# TesterMotorFaulhaber.net
KiCad netlist of a schematic drawn in EAGLE
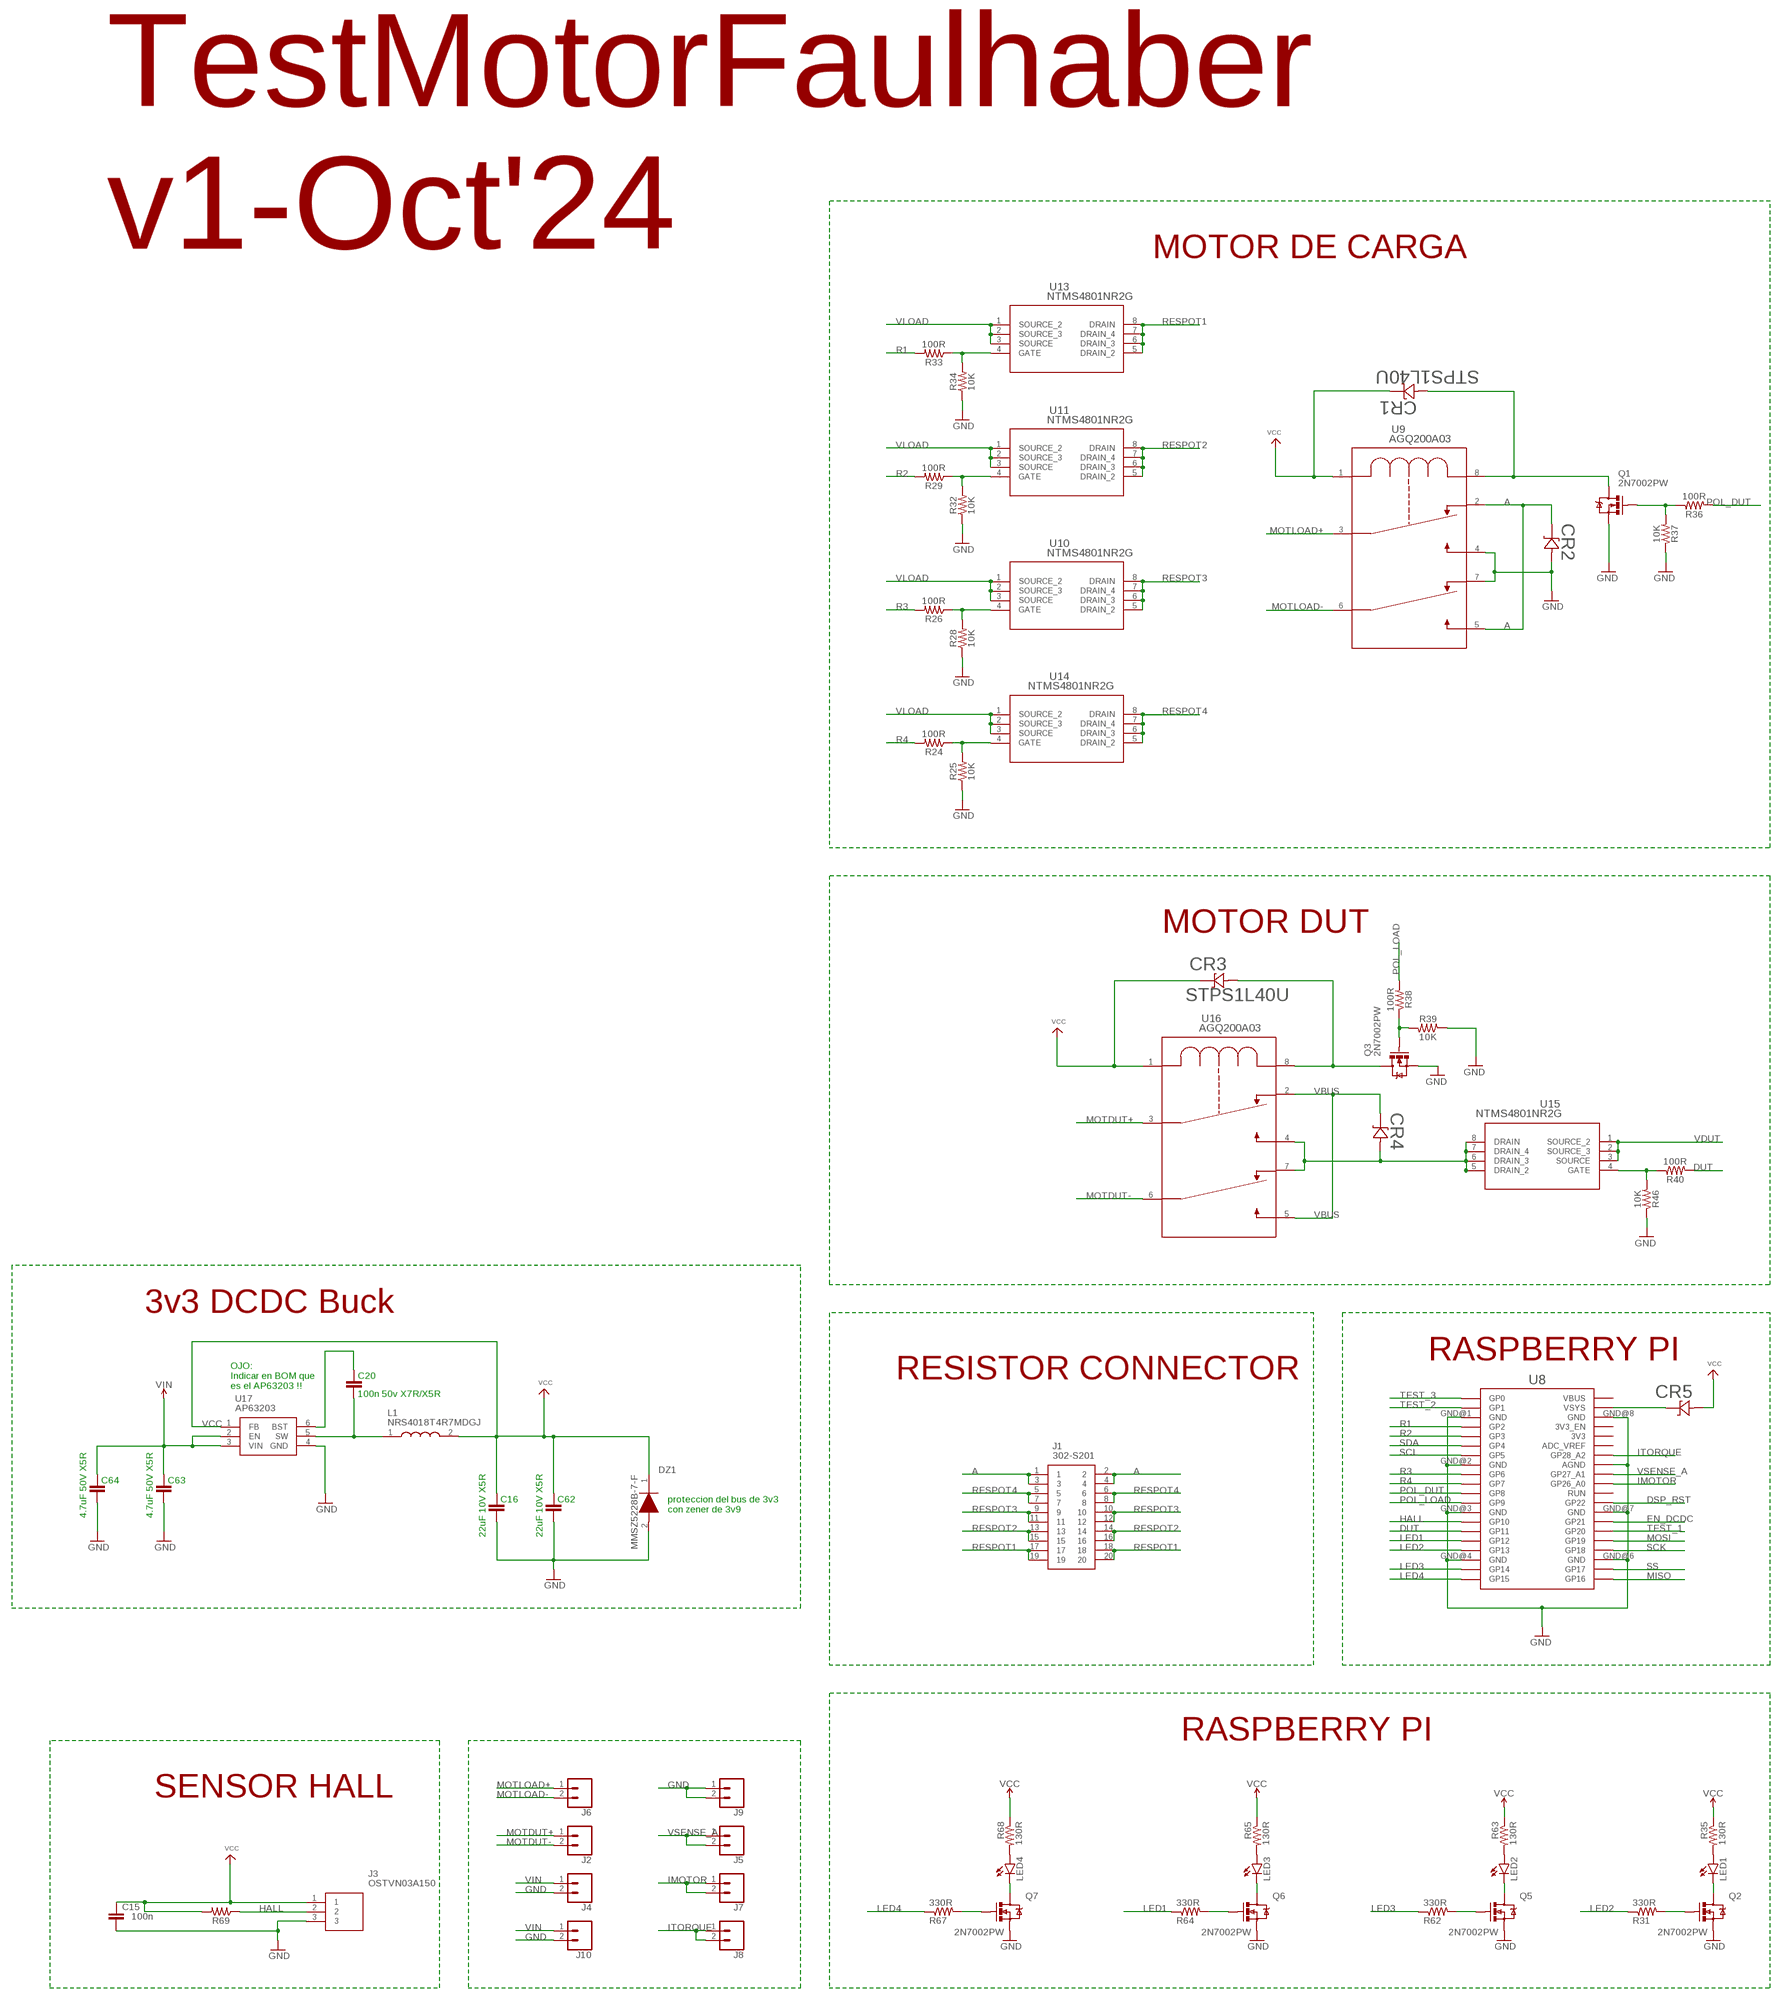
[diagram p0: schematic, sheet 1, part 1 of 2]
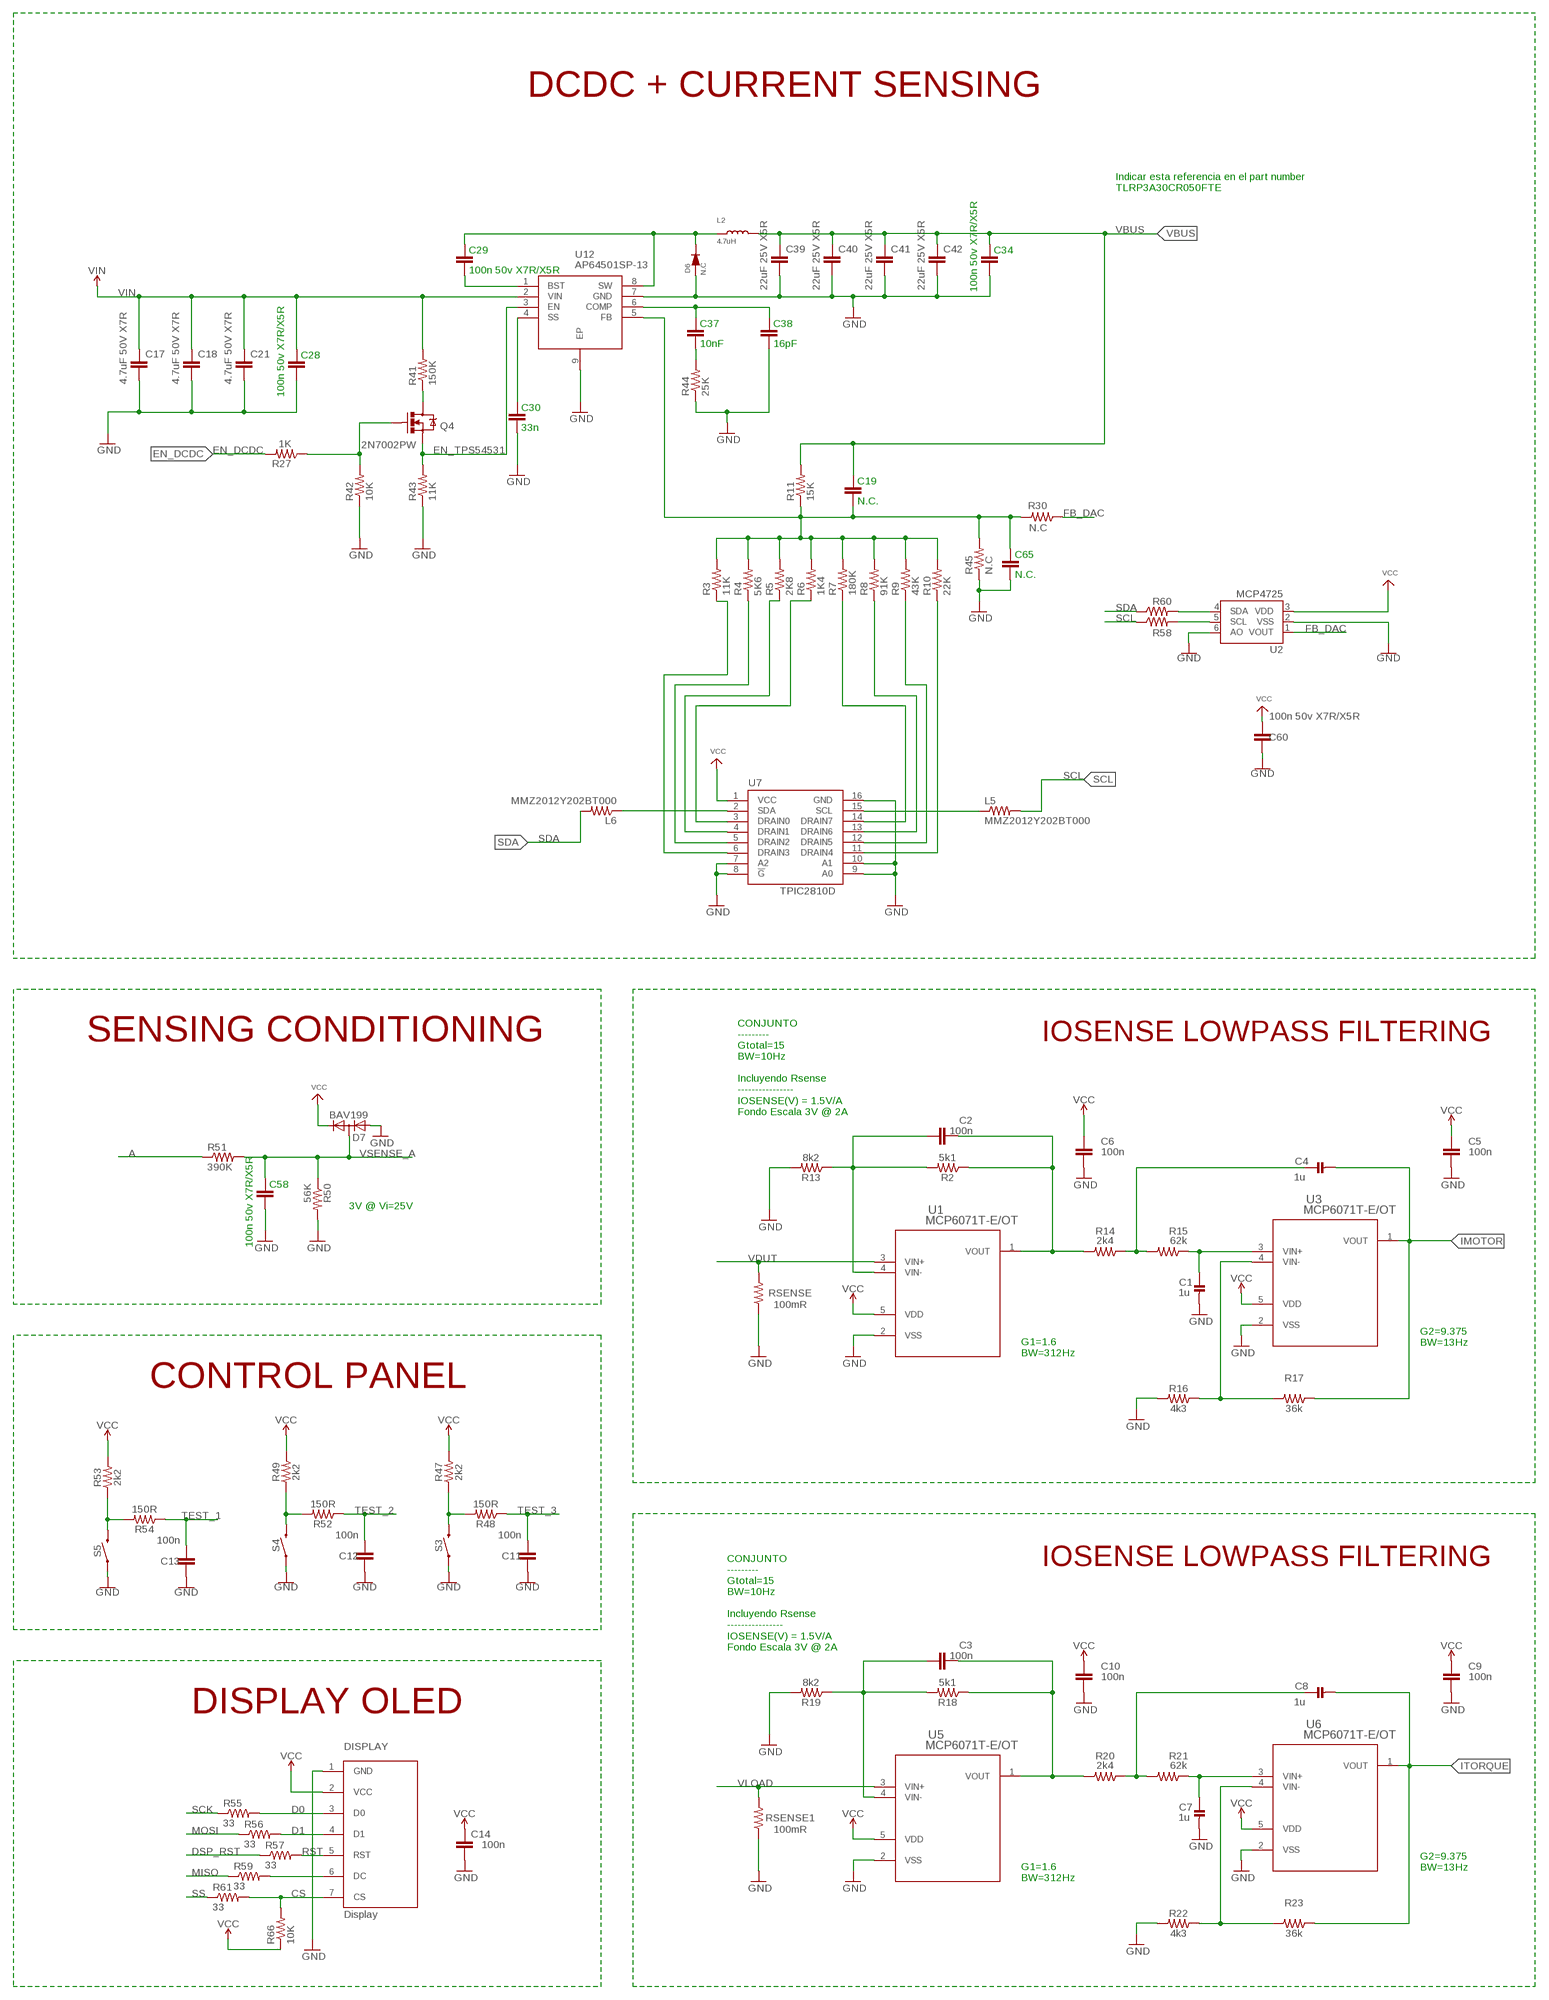
[diagram p1: schematic, sheet 1, part 2 of 2]

(export (version "E")
  (design (tool "Eeschema 10.0.6"))
  (components
    (comp (ref "C1")
      (value "1u")
      (footprint "eagle-import:0603-NO")
      (libsource (lib "eagle-import") (part "CAP_CERAMIC0603_NO"))
    )
    (comp (ref "C2")
      (value "100n")
      (footprint "eagle-import:0603")
      (libsource (lib "eagle-import") (part "0.1UF-0603-25V-(+80/-20%)"))
    )
    (comp (ref "C3")
      (value "100n")
      (footprint "eagle-import:0603")
      (libsource (lib "eagle-import") (part "0.1UF-0603-25V-(+80/-20%)"))
    )
    (comp (ref "C4")
      (value "1u")
      (footprint "eagle-import:0603-NO")
      (libsource (lib "eagle-import") (part "CAP_CERAMIC0603_NO"))
    )
    (comp (ref "C5")
      (value "100n")
      (footprint "eagle-import:0603")
      (libsource (lib "eagle-import") (part "0.1UF-0603-25V-(+80/-20%)"))
    )
    (comp (ref "C6")
      (value "100n")
      (footprint "eagle-import:0603")
      (libsource (lib "eagle-import") (part "0.1UF-0603-25V-(+80/-20%)"))
    )
    (comp (ref "C7")
      (value "1u")
      (footprint "eagle-import:0603-NO")
      (libsource (lib "eagle-import") (part "CAP_CERAMIC0603_NO"))
    )
    (comp (ref "C8")
      (value "1u")
      (footprint "eagle-import:0603-NO")
      (libsource (lib "eagle-import") (part "CAP_CERAMIC0603_NO"))
    )
    (comp (ref "C9")
      (value "100n")
      (footprint "eagle-import:0603")
      (libsource (lib "eagle-import") (part "0.1UF-0603-25V-(+80/-20%)"))
    )
    (comp (ref "C10")
      (value "100n")
      (footprint "eagle-import:0603")
      (libsource (lib "eagle-import") (part "0.1UF-0603-25V-(+80/-20%)"))
    )
    (comp (ref "C11")
      (value "100n")
      (footprint "eagle-import:0805")
      (libsource (lib "eagle-import") (part "1.0UF-0805-25V-(+80/-20%)"))
    )
    (comp (ref "C12")
      (value "100n")
      (footprint "eagle-import:0805")
      (libsource (lib "eagle-import") (part "1.0UF-0805-25V-(+80/-20%)"))
    )
    (comp (ref "C13")
      (value "100n")
      (footprint "eagle-import:0805")
      (libsource (lib "eagle-import") (part "1.0UF-0805-25V-(+80/-20%)"))
    )
    (comp (ref "C14")
      (value "100n")
      (footprint "eagle-import:0805")
      (libsource (lib "eagle-import") (part "1.0UF-0805-25V-(+80/-20%)"))
    )
    (comp (ref "C15")
      (value "100n")
      (footprint "eagle-import:0805")
      (libsource (lib "eagle-import") (part "1.0UF-0805-25V-(+80/-20%)"))
    )
    (comp (ref "C16")
      (value "22uF 10V X5R")
      (footprint "eagle-import:0805")
      (libsource (lib "eagle-import") (part "CAP0805"))
    )
    (comp (ref "C17")
      (value "4.7uF 50V X7R")
      (footprint "eagle-import:1210")
      (libsource (lib "eagle-import") (part "CAP1210"))
    )
    (comp (ref "C18")
      (value "4.7uF 50V X7R")
      (footprint "eagle-import:1210")
      (libsource (lib "eagle-import") (part "CAP1210"))
    )
    (comp (ref "C19")
      (value "N.C.")
      (footprint "eagle-import:0805")
      (libsource (lib "eagle-import") (part "CAP0805"))
    )
    (comp (ref "C20")
      (value "100n 50v X7R/X5R")
      (footprint "eagle-import:0805")
      (libsource (lib "eagle-import") (part "CAP0805"))
    )
    (comp (ref "C21")
      (value "4.7uF 50V X7R")
      (footprint "eagle-import:1210")
      (libsource (lib "eagle-import") (part "CAP1210"))
    )
    (comp (ref "C28")
      (value "100n 50v X7R/X5R")
      (footprint "eagle-import:0805")
      (libsource (lib "eagle-import") (part "CAP0805"))
    )
    (comp (ref "C29")
      (value "100n 50v X7R/X5R")
      (footprint "eagle-import:0805")
      (libsource (lib "eagle-import") (part "CAP0805"))
    )
    (comp (ref "C30")
      (value "33n")
      (footprint "eagle-import:0805")
      (libsource (lib "eagle-import") (part "CAP0805"))
    )
    (comp (ref "C34")
      (value "100n 50v X7R/X5R")
      (footprint "eagle-import:0805")
      (libsource (lib "eagle-import") (part "CAP0805"))
    )
    (comp (ref "C37")
      (value "10nF")
      (footprint "eagle-import:0805")
      (libsource (lib "eagle-import") (part "CAP0805"))
    )
    (comp (ref "C38")
      (value "16pF")
      (footprint "eagle-import:0805")
      (libsource (lib "eagle-import") (part "CAP0805"))
    )
    (comp (ref "C39")
      (value "22uF 25V X5R")
      (footprint "eagle-import:1210")
      (libsource (lib "eagle-import") (part "CAP1210"))
    )
    (comp (ref "C40")
      (value "22uF 25V X5R")
      (footprint "eagle-import:1210")
      (libsource (lib "eagle-import") (part "CAP1210"))
    )
    (comp (ref "C41")
      (value "22uF 25V X5R")
      (footprint "eagle-import:1210")
      (libsource (lib "eagle-import") (part "CAP1210"))
    )
    (comp (ref "C42")
      (value "22uF 25V X5R")
      (footprint "eagle-import:1210")
      (libsource (lib "eagle-import") (part "CAP1210"))
    )
    (comp (ref "C58")
      (value "100n 50v X7R/X5R")
      (footprint "eagle-import:0805")
      (libsource (lib "eagle-import") (part "CAP0805"))
    )
    (comp (ref "C60")
      (value "100n 50v X7R/X5R")
      (footprint "eagle-import:0805")
      (libsource (lib "eagle-import") (part "CAP0805"))
    )
    (comp (ref "C62")
      (value "22uF 10V X5R")
      (footprint "eagle-import:0805")
      (libsource (lib "eagle-import") (part "CAP0805"))
    )
    (comp (ref "C63")
      (value "4.7uF 50V X5R")
      (footprint "eagle-import:0805")
      (libsource (lib "eagle-import") (part "CAP0805"))
    )
    (comp (ref "C64")
      (value "4.7uF 50V X5R")
      (footprint "eagle-import:0805")
      (libsource (lib "eagle-import") (part "CAP0805"))
    )
    (comp (ref "C65")
      (value "N.C.")
      (footprint "eagle-import:0805")
      (libsource (lib "eagle-import") (part "CAP0805"))
    )
    (comp (ref "CR1")
      (value "STPS1L40U")
      (footprint "eagle-import:SMB_STM")
      (fields (field (name "COPYRIGHT") "Copyright (C) 2024 Ultra Librarian. All rights reserved."))
      (libsource (lib "eagle-import") (part "STPS1L40U"))
    )
    (comp (ref "CR2")
      (value "STPS1L40U")
      (footprint "eagle-import:SMB_STM")
      (fields (field (name "COPYRIGHT") "Copyright (C) 2024 Ultra Librarian. All rights reserved."))
      (libsource (lib "eagle-import") (part "STPS1L40U"))
    )
    (comp (ref "CR3")
      (value "STPS1L40U")
      (footprint "eagle-import:SMB_STM")
      (fields (field (name "COPYRIGHT") "Copyright (C) 2024 Ultra Librarian. All rights reserved."))
      (libsource (lib "eagle-import") (part "STPS1L40U"))
    )
    (comp (ref "CR4")
      (value "STPS1L40U")
      (footprint "eagle-import:SMB_STM")
      (fields (field (name "COPYRIGHT") "Copyright (C) 2024 Ultra Librarian. All rights reserved."))
      (libsource (lib "eagle-import") (part "STPS1L40U"))
    )
    (comp (ref "CR5")
      (value "STPS1L40U")
      (footprint "eagle-import:SMB_STM")
      (fields (field (name "COPYRIGHT") "Copyright (C) 2024 Ultra Librarian. All rights reserved."))
      (libsource (lib "eagle-import") (part "STPS1L40U"))
    )
    (comp (ref "D6")
      (value "N.C")
      (footprint "eagle-import:DO-214AB")
      (libsource (lib "eagle-import") (part "DSMC"))
    )
    (comp (ref "D7")
      (value "BAV199")
      (footprint "eagle-import:SOT23")
      (libsource (lib "eagle-import") (part "BAV199"))
    )
    (comp (ref "DISPLAY")
      (value "Display")
      (footprint "eagle-import:OLED_LCD")
      (libsource (lib "eagle-import") (part "OLED_LCD"))
    )
    (comp (ref "DZ1")
      (value "MMSZ5228B-7-F")
      (footprint "eagle-import:SODFL3518X115N")
      (libsource (lib "eagle-import") (part "MMSZ5228B-7-F"))
    )
    (comp (ref "J1")
      (value "302-S201")
      (footprint "eagle-import:SHDR20W66P254_2X10_3300X905X90")
      (libsource (lib "eagle-import") (part "302-S201"))
    )
    (comp (ref "J2")
      (value "CONN_02")
      (footprint "eagle-import:1X02")
      (libsource (lib "eagle-import") (part "CONN_02"))
    )
    (comp (ref "J3")
      (value "OSTVN03A150")
      (footprint "eagle-import:OSTVN03A150")
      (libsource (lib "eagle-import") (part "OSTVN03A150"))
    )
    (comp (ref "J4")
      (value "CONN_02")
      (footprint "eagle-import:1X02")
      (libsource (lib "eagle-import") (part "CONN_02"))
    )
    (comp (ref "J5")
      (value "CONN_02")
      (footprint "eagle-import:1X02")
      (libsource (lib "eagle-import") (part "CONN_02"))
    )
    (comp (ref "J6")
      (value "CONN_02")
      (footprint "eagle-import:1X02")
      (libsource (lib "eagle-import") (part "CONN_02"))
    )
    (comp (ref "J7")
      (value "CONN_02")
      (footprint "eagle-import:1X02")
      (libsource (lib "eagle-import") (part "CONN_02"))
    )
    (comp (ref "J8")
      (value "CONN_02")
      (footprint "eagle-import:1X02")
      (libsource (lib "eagle-import") (part "CONN_02"))
    )
    (comp (ref "J9")
      (value "CONN_02")
      (footprint "eagle-import:1X02")
      (libsource (lib "eagle-import") (part "CONN_02"))
    )
    (comp (ref "J10")
      (value "CONN_02")
      (footprint "eagle-import:1X02")
      (libsource (lib "eagle-import") (part "CONN_02"))
    )
    (comp (ref "L1")
      (value "NRS4018T4R7MDGJ")
      (footprint "eagle-import:NRS4018T100MDGJ")
      (fields (field (name "MOUSER_PART_NUMBER") "963-NRS4018T4R7MDGJ"))
      (libsource (lib "eagle-import") (part "NRS4018T4R7MDGJ"))
    )
    (comp (ref "L2")
      (value "4.7uH")
      (footprint "eagle-import:WE-LHMI")
      (libsource (lib "eagle-import") (part "L74437368047"))
    )
    (comp (ref "L5")
      (value "MMZ2012Y202BT000")
      (footprint "eagle-import:0805")
      (libsource (lib "eagle-import") (part "RESISTOR0805-RES"))
    )
    (comp (ref "L6")
      (value "MMZ2012Y202BT000")
      (footprint "eagle-import:0805")
      (libsource (lib "eagle-import") (part "RESISTOR0805-RES"))
    )
    (comp (ref "LED1")
      (value "LED3MM")
      (footprint "eagle-import:LED3MM")
      (libsource (lib "eagle-import") (part "LED3MM"))
    )
    (comp (ref "LED2")
      (value "LED3MM")
      (footprint "eagle-import:LED3MM")
      (libsource (lib "eagle-import") (part "LED3MM"))
    )
    (comp (ref "LED3")
      (value "LED3MM")
      (footprint "eagle-import:LED3MM")
      (libsource (lib "eagle-import") (part "LED3MM"))
    )
    (comp (ref "LED4")
      (value "LED3MM")
      (footprint "eagle-import:LED3MM")
      (libsource (lib "eagle-import") (part "LED3MM"))
    )
    (comp (ref "Q1")
      (value "2N7002PW")
      (footprint "eagle-import:SOT323")
      (libsource (lib "eagle-import") (part "MOSFET-NCHANNEL2N7002PW"))
    )
    (comp (ref "Q2")
      (value "2N7002PW")
      (footprint "eagle-import:SOT323")
      (libsource (lib "eagle-import") (part "MOSFET-NCHANNEL2N7002PW"))
    )
    (comp (ref "Q3")
      (value "2N7002PW")
      (footprint "eagle-import:SOT323")
      (libsource (lib "eagle-import") (part "MOSFET-NCHANNEL2N7002PW"))
    )
    (comp (ref "Q4")
      (value "2N7002PW")
      (footprint "eagle-import:SOT323")
      (libsource (lib "eagle-import") (part "MOSFET-NCHANNEL2N7002PW"))
    )
    (comp (ref "Q5")
      (value "2N7002PW")
      (footprint "eagle-import:SOT323")
      (libsource (lib "eagle-import") (part "MOSFET-NCHANNEL2N7002PW"))
    )
    (comp (ref "Q6")
      (value "2N7002PW")
      (footprint "eagle-import:SOT323")
      (libsource (lib "eagle-import") (part "MOSFET-NCHANNEL2N7002PW"))
    )
    (comp (ref "Q7")
      (value "2N7002PW")
      (footprint "eagle-import:SOT323")
      (libsource (lib "eagle-import") (part "MOSFET-NCHANNEL2N7002PW"))
    )
    (comp (ref "R2")
      (value "5k1")
      (footprint "eagle-import:0805")
      (libsource (lib "eagle-import") (part "RESISTOR0805"))
    )
    (comp (ref "R3")
      (value "11K")
      (footprint "eagle-import:0805")
      (libsource (lib "eagle-import") (part "RESISTOR0805"))
    )
    (comp (ref "R4")
      (value "5K6")
      (footprint "eagle-import:0805")
      (libsource (lib "eagle-import") (part "RESISTOR0805"))
    )
    (comp (ref "R5")
      (value "2K8")
      (footprint "eagle-import:0805")
      (libsource (lib "eagle-import") (part "RESISTOR0805"))
    )
    (comp (ref "R6")
      (value "1K4")
      (footprint "eagle-import:0805")
      (libsource (lib "eagle-import") (part "RESISTOR0805"))
    )
    (comp (ref "R7")
      (value "180K")
      (footprint "eagle-import:0805")
      (libsource (lib "eagle-import") (part "RESISTOR0805"))
    )
    (comp (ref "R8")
      (value "91K")
      (footprint "eagle-import:0805")
      (libsource (lib "eagle-import") (part "RESISTOR0805"))
    )
    (comp (ref "R9")
      (value "43K")
      (footprint "eagle-import:0805")
      (libsource (lib "eagle-import") (part "RESISTOR0805"))
    )
    (comp (ref "R10")
      (value "22K")
      (footprint "eagle-import:0805")
      (libsource (lib "eagle-import") (part "RESISTOR0805"))
    )
    (comp (ref "R11")
      (value "15K")
      (footprint "eagle-import:0805")
      (libsource (lib "eagle-import") (part "RESISTOR0805"))
    )
    (comp (ref "R13")
      (value "8k2")
      (footprint "eagle-import:0805")
      (libsource (lib "eagle-import") (part "RESISTOR0805"))
    )
    (comp (ref "R14")
      (value "2k4")
      (footprint "eagle-import:0805")
      (libsource (lib "eagle-import") (part "RESISTOR0805"))
    )
    (comp (ref "R15")
      (value "62k")
      (footprint "eagle-import:0805")
      (libsource (lib "eagle-import") (part "RESISTOR0805"))
    )
    (comp (ref "R16")
      (value "4k3")
      (footprint "eagle-import:0805")
      (libsource (lib "eagle-import") (part "RESISTOR0805"))
    )
    (comp (ref "R17")
      (value "36k")
      (footprint "eagle-import:0805")
      (libsource (lib "eagle-import") (part "RESISTOR0805"))
    )
    (comp (ref "R18")
      (value "5k1")
      (footprint "eagle-import:0805")
      (libsource (lib "eagle-import") (part "RESISTOR0805"))
    )
    (comp (ref "R19")
      (value "8k2")
      (footprint "eagle-import:0805")
      (libsource (lib "eagle-import") (part "RESISTOR0805"))
    )
    (comp (ref "R20")
      (value "2k4")
      (footprint "eagle-import:0805")
      (libsource (lib "eagle-import") (part "RESISTOR0805"))
    )
    (comp (ref "R21")
      (value "62k")
      (footprint "eagle-import:0805")
      (libsource (lib "eagle-import") (part "RESISTOR0805"))
    )
    (comp (ref "R22")
      (value "4k3")
      (footprint "eagle-import:0805")
      (libsource (lib "eagle-import") (part "RESISTOR0805"))
    )
    (comp (ref "R23")
      (value "36k")
      (footprint "eagle-import:0805")
      (libsource (lib "eagle-import") (part "RESISTOR0805"))
    )
    (comp (ref "R24")
      (value "100R")
      (footprint "eagle-import:0805")
      (libsource (lib "eagle-import") (part "RESISTOR0805"))
    )
    (comp (ref "R25")
      (value "10K")
      (footprint "eagle-import:0805")
      (libsource (lib "eagle-import") (part "RESISTOR0805"))
    )
    (comp (ref "R26")
      (value "100R")
      (footprint "eagle-import:0805")
      (libsource (lib "eagle-import") (part "RESISTOR0805"))
    )
    (comp (ref "R27")
      (value "1K")
      (footprint "eagle-import:0805")
      (libsource (lib "eagle-import") (part "RESISTOR0805"))
    )
    (comp (ref "R28")
      (value "10K")
      (footprint "eagle-import:0805")
      (libsource (lib "eagle-import") (part "RESISTOR0805"))
    )
    (comp (ref "R29")
      (value "100R")
      (footprint "eagle-import:0805")
      (libsource (lib "eagle-import") (part "RESISTOR0805"))
    )
    (comp (ref "R30")
      (value "N.C")
      (footprint "eagle-import:0805")
      (libsource (lib "eagle-import") (part "RESISTOR0805"))
    )
    (comp (ref "R31")
      (value "330R")
      (footprint "eagle-import:0805")
      (libsource (lib "eagle-import") (part "RESISTOR0805"))
    )
    (comp (ref "R32")
      (value "10K")
      (footprint "eagle-import:0805")
      (libsource (lib "eagle-import") (part "RESISTOR0805"))
    )
    (comp (ref "R33")
      (value "100R")
      (footprint "eagle-import:0805")
      (libsource (lib "eagle-import") (part "RESISTOR0805"))
    )
    (comp (ref "R34")
      (value "10K")
      (footprint "eagle-import:0805")
      (libsource (lib "eagle-import") (part "RESISTOR0805"))
    )
    (comp (ref "R35")
      (value "130R")
      (footprint "eagle-import:0805")
      (libsource (lib "eagle-import") (part "RESISTOR0805"))
    )
    (comp (ref "R36")
      (value "100R")
      (footprint "eagle-import:0805")
      (libsource (lib "eagle-import") (part "RESISTOR0805"))
    )
    (comp (ref "R37")
      (value "10K")
      (footprint "eagle-import:0805")
      (libsource (lib "eagle-import") (part "RESISTOR0805"))
    )
    (comp (ref "R38")
      (value "100R")
      (footprint "eagle-import:0805")
      (libsource (lib "eagle-import") (part "RESISTOR0805"))
    )
    (comp (ref "R39")
      (value "10K")
      (footprint "eagle-import:0805")
      (libsource (lib "eagle-import") (part "RESISTOR0805"))
    )
    (comp (ref "R40")
      (value "100R")
      (footprint "eagle-import:0805")
      (libsource (lib "eagle-import") (part "RESISTOR0805"))
    )
    (comp (ref "R41")
      (value "150K")
      (footprint "eagle-import:0805")
      (libsource (lib "eagle-import") (part "RESISTOR0805"))
    )
    (comp (ref "R42")
      (value "10K")
      (footprint "eagle-import:0805")
      (libsource (lib "eagle-import") (part "RESISTOR0805"))
    )
    (comp (ref "R43")
      (value "11K")
      (footprint "eagle-import:0805")
      (libsource (lib "eagle-import") (part "RESISTOR0805"))
    )
    (comp (ref "R44")
      (value "25K")
      (footprint "eagle-import:0805")
      (libsource (lib "eagle-import") (part "RESISTOR0805"))
    )
    (comp (ref "R45")
      (value "N.C")
      (footprint "eagle-import:0805")
      (libsource (lib "eagle-import") (part "RESISTOR0805"))
    )
    (comp (ref "R46")
      (value "10K")
      (footprint "eagle-import:0805")
      (libsource (lib "eagle-import") (part "RESISTOR0805"))
    )
    (comp (ref "R47")
      (value "2k2")
      (footprint "eagle-import:0805")
      (libsource (lib "eagle-import") (part "RESISTOR0805"))
    )
    (comp (ref "R48")
      (value "150R")
      (footprint "eagle-import:0805")
      (libsource (lib "eagle-import") (part "RESISTOR0805"))
    )
    (comp (ref "R49")
      (value "2k2")
      (footprint "eagle-import:0805")
      (libsource (lib "eagle-import") (part "RESISTOR0805"))
    )
    (comp (ref "R50")
      (value "56K")
      (footprint "eagle-import:0805")
      (libsource (lib "eagle-import") (part "RESISTOR0805"))
    )
    (comp (ref "R51")
      (value "390K")
      (footprint "eagle-import:0805")
      (libsource (lib "eagle-import") (part "RESISTOR0805"))
    )
    (comp (ref "R52")
      (value "150R")
      (footprint "eagle-import:0805")
      (libsource (lib "eagle-import") (part "RESISTOR0805"))
    )
    (comp (ref "R53")
      (value "2k2")
      (footprint "eagle-import:0805")
      (libsource (lib "eagle-import") (part "RESISTOR0805"))
    )
    (comp (ref "R54")
      (value "150R")
      (footprint "eagle-import:0805")
      (libsource (lib "eagle-import") (part "RESISTOR0805"))
    )
    (comp (ref "R55")
      (value "33")
      (footprint "eagle-import:0805")
      (libsource (lib "eagle-import") (part "RESISTOR0805"))
    )
    (comp (ref "R56")
      (value "33")
      (footprint "eagle-import:0805")
      (libsource (lib "eagle-import") (part "RESISTOR0805"))
    )
    (comp (ref "R57")
      (value "33")
      (footprint "eagle-import:0805")
      (libsource (lib "eagle-import") (part "RESISTOR0805"))
    )
    (comp (ref "R58")
      (value "N.C")
      (footprint "eagle-import:0805")
      (libsource (lib "eagle-import") (part "RESISTOR0805"))
    )
    (comp (ref "R59")
      (value "33")
      (footprint "eagle-import:0805")
      (libsource (lib "eagle-import") (part "RESISTOR0805"))
    )
    (comp (ref "R60")
      (value "N.C")
      (footprint "eagle-import:0805")
      (libsource (lib "eagle-import") (part "RESISTOR0805"))
    )
    (comp (ref "R61")
      (value "33")
      (footprint "eagle-import:0805")
      (libsource (lib "eagle-import") (part "RESISTOR0805"))
    )
    (comp (ref "R62")
      (value "330R")
      (footprint "eagle-import:0805")
      (libsource (lib "eagle-import") (part "RESISTOR0805"))
    )
    (comp (ref "R63")
      (value "130R")
      (footprint "eagle-import:0805")
      (libsource (lib "eagle-import") (part "RESISTOR0805"))
    )
    (comp (ref "R64")
      (value "330R")
      (footprint "eagle-import:0805")
      (libsource (lib "eagle-import") (part "RESISTOR0805"))
    )
    (comp (ref "R65")
      (value "130R")
      (footprint "eagle-import:0805")
      (libsource (lib "eagle-import") (part "RESISTOR0805"))
    )
    (comp (ref "R66")
      (value "10K")
      (footprint "eagle-import:0805")
      (libsource (lib "eagle-import") (part "RESISTOR0805"))
    )
    (comp (ref "R67")
      (value "330R")
      (footprint "eagle-import:0805")
      (libsource (lib "eagle-import") (part "RESISTOR0805"))
    )
    (comp (ref "R68")
      (value "130R")
      (footprint "eagle-import:0805")
      (libsource (lib "eagle-import") (part "RESISTOR0805"))
    )
    (comp (ref "R69")
      (value "RESISTOR0805")
      (footprint "eagle-import:0805")
      (libsource (lib "eagle-import") (part "RESISTOR0805"))
    )
    (comp (ref "RSENSE")
      (value "100mR")
      (footprint "eagle-import:1206")
      (libsource (lib "eagle-import") (part "SparkFun-Resistors_532_RESISTOR1206"))
    )
    (comp (ref "RSENSE1")
      (value "100mR")
      (footprint "eagle-import:1206")
      (libsource (lib "eagle-import") (part "SparkFun-Resistors_532_RESISTOR1206"))
    )
    (comp (ref "S3")
      (value "MOMENTARY-SWITCH-SPST-SMD-5.2MM")
      (footprint "eagle-import:TACTILE_SWITCH_SMD_5.2MM")
      (libsource (lib "eagle-import") (part "MOMENTARY-SWITCH-SPST-SMD-5.2MM"))
    )
    (comp (ref "S4")
      (value "MOMENTARY-SWITCH-SPST-SMD-5.2MM")
      (footprint "eagle-import:TACTILE_SWITCH_SMD_5.2MM")
      (libsource (lib "eagle-import") (part "MOMENTARY-SWITCH-SPST-SMD-5.2MM"))
    )
    (comp (ref "S5")
      (value "MOMENTARY-SWITCH-SPST-SMD-5.2MM")
      (footprint "eagle-import:TACTILE_SWITCH_SMD_5.2MM")
      (libsource (lib "eagle-import") (part "MOMENTARY-SWITCH-SPST-SMD-5.2MM"))
    )
    (comp (ref "U1")
      (value "MCP6071T-E/OT")
      (footprint "eagle-import:SOT-23-5_MC_MCH")
      (fields (field (name "COPYRIGHT") "Copyright (C) 2018 Accelerated Designs. All rights reserved"))
      (libsource (lib "eagle-import") (part "MCP6071T-E/OT"))
    )
    (comp (ref "U2")
      (value "MCP4725")
      (footprint "eagle-import:SOT23-6")
      (libsource (lib "eagle-import") (part "MCP4725SOT-23"))
    )
    (comp (ref "U3")
      (value "MCP6071T-E/OT")
      (footprint "eagle-import:SOT-23-5_MC_MCH")
      (fields (field (name "COPYRIGHT") "Copyright (C) 2018 Accelerated Designs. All rights reserved"))
      (libsource (lib "eagle-import") (part "MCP6071T-E/OT"))
    )
    (comp (ref "U5")
      (value "MCP6071T-E/OT")
      (footprint "eagle-import:SOT-23-5_MC_MCH")
      (fields (field (name "COPYRIGHT") "Copyright (C) 2018 Accelerated Designs. All rights reserved"))
      (libsource (lib "eagle-import") (part "MCP6071T-E/OT"))
    )
    (comp (ref "U6")
      (value "MCP6071T-E/OT")
      (footprint "eagle-import:SOT-23-5_MC_MCH")
      (fields (field (name "COPYRIGHT") "Copyright (C) 2018 Accelerated Designs. All rights reserved"))
      (libsource (lib "eagle-import") (part "MCP6071T-E/OT"))
    )
    (comp (ref "U7")
      (value "TPIC2810D")
      (footprint "eagle-import:SO16")
      (libsource (lib "eagle-import") (part "TPIC2810D"))
    )
    (comp (ref "U8")
      (value "RPI_PICO_IG-TH")
      (footprint "eagle-import:RPI_PICO_TH")
      (libsource (lib "eagle-import") (part "RPI_PICO_IG-TH"))
    )
    (comp (ref "U9")
      (value "AGQ200A03")
      (footprint "eagle-import:RELAY_AGQ_A_PAN")
      (fields (field (name "COPYRIGHT") "Copyright (C) 2024 Ultra Librarian. All rights reserved."))
      (libsource (lib "eagle-import") (part "AGQ200A03"))
    )
    (comp (ref "U10")
      (value "NTMS4801NR2G")
      (footprint "eagle-import:SOIC8_4X5_ONS")
      (fields (field (name "COPYRIGHT") "Copyright (C) 2024 Ultra Librarian. All rights reserved."))
      (libsource (lib "eagle-import") (part "NTMS4801NR2G"))
    )
    (comp (ref "U11")
      (value "NTMS4801NR2G")
      (footprint "eagle-import:SOIC8_4X5_ONS")
      (fields (field (name "COPYRIGHT") "Copyright (C) 2024 Ultra Librarian. All rights reserved."))
      (libsource (lib "eagle-import") (part "NTMS4801NR2G"))
    )
    (comp (ref "U12")
      (value "AP64501SP-13")
      (footprint "eagle-import:SOIC127P600X163-9N")
      (fields (field (name "MOUSER_PART_NUMBER") "621-AP64501SP-13"))
      (libsource (lib "eagle-import") (part "AP64501SP-13"))
    )
    (comp (ref "U13")
      (value "NTMS4801NR2G")
      (footprint "eagle-import:SOIC8_4X5_ONS")
      (fields (field (name "COPYRIGHT") "Copyright (C) 2024 Ultra Librarian. All rights reserved."))
      (libsource (lib "eagle-import") (part "NTMS4801NR2G"))
    )
    (comp (ref "U14")
      (value "NTMS4801NR2G")
      (footprint "eagle-import:SOIC8_4X5_ONS")
      (fields (field (name "COPYRIGHT") "Copyright (C) 2024 Ultra Librarian. All rights reserved."))
      (libsource (lib "eagle-import") (part "NTMS4801NR2G"))
    )
    (comp (ref "U15")
      (value "NTMS4801NR2G")
      (footprint "eagle-import:SOIC8_4X5_ONS")
      (fields (field (name "COPYRIGHT") "Copyright (C) 2024 Ultra Librarian. All rights reserved."))
      (libsource (lib "eagle-import") (part "NTMS4801NR2G"))
    )
    (comp (ref "U16")
      (value "AGQ200A03")
      (footprint "eagle-import:RELAY_AGQ_A_PAN")
      (fields (field (name "COPYRIGHT") "Copyright (C) 2024 Ultra Librarian. All rights reserved."))
      (libsource (lib "eagle-import") (part "AGQ200A03"))
    )
    (comp (ref "U17")
      (value "AP63203")
      (footprint "eagle-import:SOT95P280X100-6N")
      (fields
        (field (name "ARROW_PART_NUMBER") "AP63201WU-7")
        (field (name "MOUSER_PART_NUMBER") "621-AP63201WU-7")
      )
      (libsource (lib "eagle-import") (part "AP63201WU-7"))
    )
  )
  (nets
    (net (code "1") (name "/A") (class "Default")
      (node (ref "CR2") (pin "2") (pinfunction "2_2") (pintype "passive"))
      (node (ref "J1") (pin "1") (pinfunction "1_1") (pintype "bidirectional"))
      (node (ref "J1") (pin "2") (pinfunction "2_2") (pintype "bidirectional"))
      (node (ref "J1") (pin "3") (pinfunction "3_3") (pintype "bidirectional"))
      (node (ref "J1") (pin "4") (pinfunction "4_4") (pintype "bidirectional"))
      (node (ref "R51") (pin "1") (pinfunction "1_1") (pintype "passive"))
      (node (ref "U9") (pin "2") (pinfunction "5_2") (pintype "passive"))
      (node (ref "U9") (pin "5") (pinfunction "3_5") (pintype "passive"))
    )
    (net (code "2") (name "/CS") (class "Default")
      (node (ref "DISPLAY") (pin "7") (pinfunction "CS_7") (pintype "bidirectional"))
      (node (ref "R61") (pin "2") (pinfunction "2_2") (pintype "passive"))
      (node (ref "R66") (pin "2") (pinfunction "2_2") (pintype "passive"))
    )
    (net (code "3") (name "/D0") (class "Default")
      (node (ref "DISPLAY") (pin "3") (pinfunction "D0_3") (pintype "bidirectional"))
      (node (ref "R55") (pin "2") (pinfunction "2_2") (pintype "passive"))
    )
    (net (code "4") (name "/D1") (class "Default")
      (node (ref "DISPLAY") (pin "4") (pinfunction "D1_4") (pintype "bidirectional"))
      (node (ref "R56") (pin "2") (pinfunction "2_2") (pintype "passive"))
    )
    (net (code "5") (name "/DSP_RST") (class "Default")
      (node (ref "R57") (pin "1") (pinfunction "1_1") (pintype "passive"))
      (node (ref "U8") (pin "GP22") (pinfunction "GP22_GP22") (pintype "bidirectional"))
    )
    (net (code "6") (name "/DUT") (class "Default")
      (node (ref "R40") (pin "2") (pinfunction "2_2") (pintype "passive"))
      (node (ref "U8") (pin "GP11") (pinfunction "GP11_GP11") (pintype "bidirectional"))
    )
    (net (code "7") (name "/EN_TPS54531") (class "Default")
      (node (ref "Q4") (pin "2") (pinfunction "S_2") (pintype "passive"))
      (node (ref "R43") (pin "2") (pinfunction "2_2") (pintype "passive"))
      (node (ref "U12") (pin "3") (pinfunction "EN_3") (pintype "bidirectional"))
    )
    (net (code "8") (name "/FB_DAC") (class "Default")
      (node (ref "R30") (pin "1") (pinfunction "1_1") (pintype "passive"))
      (node (ref "U2") (pin "1") (pinfunction "VOUT_1") (pintype "bidirectional"))
    )
    (net (code "9") (name "/HALL") (class "Default")
      (node (ref "J3") (pin "2") (pinfunction "2_2") (pintype "bidirectional"))
      (node (ref "R69") (pin "1") (pinfunction "1_1") (pintype "passive"))
      (node (ref "U8") (pin "GP10") (pinfunction "GP10_GP10") (pintype "bidirectional"))
    )
    (net (code "10") (name "/LED1") (class "Default")
      (node (ref "R64") (pin "1") (pinfunction "1_1") (pintype "passive"))
      (node (ref "U8") (pin "GP12") (pinfunction "GP12_GP12") (pintype "bidirectional"))
    )
    (net (code "11") (name "/LED2") (class "Default")
      (node (ref "R31") (pin "1") (pinfunction "1_1") (pintype "passive"))
      (node (ref "U8") (pin "GP13") (pinfunction "GP13_GP13") (pintype "bidirectional"))
    )
    (net (code "12") (name "/LED3") (class "Default")
      (node (ref "R62") (pin "1") (pinfunction "1_1") (pintype "passive"))
      (node (ref "U8") (pin "GP14") (pinfunction "GP14_GP14") (pintype "bidirectional"))
    )
    (net (code "13") (name "/LED4") (class "Default")
      (node (ref "R67") (pin "1") (pinfunction "1_1") (pintype "passive"))
      (node (ref "U8") (pin "GP15") (pinfunction "GP15_GP15") (pintype "bidirectional"))
    )
    (net (code "14") (name "/MISO") (class "Default")
      (node (ref "R59") (pin "1") (pinfunction "1_1") (pintype "passive"))
      (node (ref "U8") (pin "GP16") (pinfunction "GP16_GP16") (pintype "bidirectional"))
    )
    (net (code "15") (name "/MOSI") (class "Default")
      (node (ref "R56") (pin "1") (pinfunction "1_1") (pintype "passive"))
      (node (ref "U8") (pin "GP19") (pinfunction "GP19_GP19") (pintype "bidirectional"))
    )
    (net (code "16") (name "/MOTDUT+") (class "Default")
      (node (ref "J2") (pin "1") (pinfunction "1_1") (pintype "passive"))
      (node (ref "U16") (pin "3") (pinfunction "3_2_3") (pintype "passive"))
    )
    (net (code "17") (name "/MOTDUT-") (class "Default")
      (node (ref "J2") (pin "2") (pinfunction "2_2") (pintype "passive"))
      (node (ref "U16") (pin "6") (pinfunction "6_6") (pintype "passive"))
    )
    (net (code "18") (name "/MOTLOAD+") (class "Default")
      (node (ref "J6") (pin "1") (pinfunction "1_1") (pintype "passive"))
      (node (ref "U9") (pin "3") (pinfunction "3_2_3") (pintype "passive"))
    )
    (net (code "19") (name "/MOTLOAD-") (class "Default")
      (node (ref "J6") (pin "2") (pinfunction "2_2") (pintype "passive"))
      (node (ref "U9") (pin "6") (pinfunction "6_6") (pintype "passive"))
    )
    (net (code "20") (name "/POL_DUT") (class "Default")
      (node (ref "R36") (pin "2") (pinfunction "2_2") (pintype "passive"))
      (node (ref "U8") (pin "GP8") (pinfunction "GP8_GP8") (pintype "bidirectional"))
    )
    (net (code "21") (name "/POL_LOAD") (class "Default")
      (node (ref "R38") (pin "2") (pinfunction "2_2") (pintype "passive"))
      (node (ref "U8") (pin "GP9") (pinfunction "GP9_GP9") (pintype "bidirectional"))
    )
    (net (code "22") (name "/R1") (class "Default")
      (node (ref "R33") (pin "2") (pinfunction "2_2") (pintype "passive"))
      (node (ref "U8") (pin "GP2") (pinfunction "GP2_GP2") (pintype "bidirectional"))
    )
    (net (code "23") (name "/R2") (class "Default")
      (node (ref "R29") (pin "2") (pinfunction "2_2") (pintype "passive"))
      (node (ref "U8") (pin "GP3") (pinfunction "GP3_GP3") (pintype "bidirectional"))
    )
    (net (code "24") (name "/R3") (class "Default")
      (node (ref "R26") (pin "2") (pinfunction "2_2") (pintype "passive"))
      (node (ref "U8") (pin "GP6") (pinfunction "GP6_GP6") (pintype "bidirectional"))
    )
    (net (code "25") (name "/R4") (class "Default")
      (node (ref "R24") (pin "2") (pinfunction "2_2") (pintype "passive"))
      (node (ref "U8") (pin "GP7") (pinfunction "GP7_GP7") (pintype "bidirectional"))
    )
    (net (code "26") (name "/RESPOT1") (class "Default")
      (node (ref "J1") (pin "17") (pinfunction "17_17") (pintype "bidirectional"))
      (node (ref "J1") (pin "18") (pinfunction "18_18") (pintype "bidirectional"))
      (node (ref "J1") (pin "19") (pinfunction "19_19") (pintype "bidirectional"))
      (node (ref "J1") (pin "20") (pinfunction "20_20") (pintype "bidirectional"))
      (node (ref "U13") (pin "5") (pinfunction "DRAIN_2_5") (pintype "passive"))
      (node (ref "U13") (pin "6") (pinfunction "DRAIN_3_6") (pintype "passive"))
      (node (ref "U13") (pin "7") (pinfunction "DRAIN_4_7") (pintype "passive"))
      (node (ref "U13") (pin "8") (pinfunction "DRAIN_8") (pintype "passive"))
    )
    (net (code "27") (name "/RESPOT2") (class "Default")
      (node (ref "J1") (pin "13") (pinfunction "13_13") (pintype "bidirectional"))
      (node (ref "J1") (pin "14") (pinfunction "14_14") (pintype "bidirectional"))
      (node (ref "J1") (pin "15") (pinfunction "15_15") (pintype "bidirectional"))
      (node (ref "J1") (pin "16") (pinfunction "16_16") (pintype "bidirectional"))
      (node (ref "U11") (pin "5") (pinfunction "DRAIN_2_5") (pintype "passive"))
      (node (ref "U11") (pin "6") (pinfunction "DRAIN_3_6") (pintype "passive"))
      (node (ref "U11") (pin "7") (pinfunction "DRAIN_4_7") (pintype "passive"))
      (node (ref "U11") (pin "8") (pinfunction "DRAIN_8") (pintype "passive"))
    )
    (net (code "28") (name "/RESPOT3") (class "Default")
      (node (ref "J1") (pin "10") (pinfunction "10_10") (pintype "bidirectional"))
      (node (ref "J1") (pin "11") (pinfunction "11_11") (pintype "bidirectional"))
      (node (ref "J1") (pin "12") (pinfunction "12_12") (pintype "bidirectional"))
      (node (ref "J1") (pin "9") (pinfunction "9_9") (pintype "bidirectional"))
      (node (ref "U10") (pin "5") (pinfunction "DRAIN_2_5") (pintype "passive"))
      (node (ref "U10") (pin "6") (pinfunction "DRAIN_3_6") (pintype "passive"))
      (node (ref "U10") (pin "7") (pinfunction "DRAIN_4_7") (pintype "passive"))
      (node (ref "U10") (pin "8") (pinfunction "DRAIN_8") (pintype "passive"))
    )
    (net (code "29") (name "/RESPOT4") (class "Default")
      (node (ref "J1") (pin "5") (pinfunction "5_5") (pintype "bidirectional"))
      (node (ref "J1") (pin "6") (pinfunction "6_6") (pintype "bidirectional"))
      (node (ref "J1") (pin "7") (pinfunction "7_7") (pintype "bidirectional"))
      (node (ref "J1") (pin "8") (pinfunction "8_8") (pintype "bidirectional"))
      (node (ref "U14") (pin "5") (pinfunction "DRAIN_2_5") (pintype "passive"))
      (node (ref "U14") (pin "6") (pinfunction "DRAIN_3_6") (pintype "passive"))
      (node (ref "U14") (pin "7") (pinfunction "DRAIN_4_7") (pintype "passive"))
      (node (ref "U14") (pin "8") (pinfunction "DRAIN_8") (pintype "passive"))
    )
    (net (code "30") (name "/RST") (class "Default")
      (node (ref "DISPLAY") (pin "5") (pinfunction "RST_5") (pintype "bidirectional"))
      (node (ref "R57") (pin "2") (pinfunction "2_2") (pintype "passive"))
    )
    (net (code "31") (name "/SCK") (class "Default")
      (node (ref "R55") (pin "1") (pinfunction "1_1") (pintype "passive"))
      (node (ref "U8") (pin "GP18") (pinfunction "GP18_GP18") (pintype "bidirectional"))
    )
    (net (code "32") (name "/SS") (class "Default")
      (node (ref "R61") (pin "1") (pinfunction "1_1") (pintype "passive"))
      (node (ref "U8") (pin "GP17") (pinfunction "GP17_GP17") (pintype "bidirectional"))
    )
    (net (code "33") (name "/TEST_1") (class "Default")
      (node (ref "C13") (pin "2") (pinfunction "2_2") (pintype "passive"))
      (node (ref "R54") (pin "1") (pinfunction "1_1") (pintype "passive"))
      (node (ref "U8") (pin "GP20") (pinfunction "GP20_GP20") (pintype "bidirectional"))
    )
    (net (code "34") (name "/TEST_2") (class "Default")
      (node (ref "C12") (pin "2") (pinfunction "2_2") (pintype "passive"))
      (node (ref "R52") (pin "1") (pinfunction "1_1") (pintype "passive"))
      (node (ref "U8") (pin "GP1") (pinfunction "GP1_GP1") (pintype "bidirectional"))
    )
    (net (code "35") (name "/TEST_3") (class "Default")
      (node (ref "C11") (pin "2") (pinfunction "2_2") (pintype "passive"))
      (node (ref "R48") (pin "1") (pinfunction "1_1") (pintype "passive"))
      (node (ref "U8") (pin "GP0") (pinfunction "GP0_GP0") (pintype "bidirectional"))
    )
    (net (code "36") (name "/VDUT") (class "Default")
      (node (ref "RSENSE") (pin "2") (pinfunction "2_2") (pintype "passive"))
      (node (ref "U1") (pin "3") (pinfunction "VIN+_3") (pintype "input"))
      (node (ref "U15") (pin "1") (pinfunction "SOURCE_2_1") (pintype "passive"))
      (node (ref "U15") (pin "2") (pinfunction "SOURCE_3_2") (pintype "passive"))
      (node (ref "U15") (pin "3") (pinfunction "SOURCE_3") (pintype "passive"))
    )
    (net (code "37") (name "/VLOAD") (class "Default")
      (node (ref "RSENSE1") (pin "2") (pinfunction "2_2") (pintype "passive"))
      (node (ref "U10") (pin "1") (pinfunction "SOURCE_2_1") (pintype "passive"))
      (node (ref "U10") (pin "2") (pinfunction "SOURCE_3_2") (pintype "passive"))
      (node (ref "U10") (pin "3") (pinfunction "SOURCE_3") (pintype "passive"))
      (node (ref "U11") (pin "1") (pinfunction "SOURCE_2_1") (pintype "passive"))
      (node (ref "U11") (pin "2") (pinfunction "SOURCE_3_2") (pintype "passive"))
      (node (ref "U11") (pin "3") (pinfunction "SOURCE_3") (pintype "passive"))
      (node (ref "U13") (pin "1") (pinfunction "SOURCE_2_1") (pintype "passive"))
      (node (ref "U13") (pin "2") (pinfunction "SOURCE_3_2") (pintype "passive"))
      (node (ref "U13") (pin "3") (pinfunction "SOURCE_3") (pintype "passive"))
      (node (ref "U14") (pin "1") (pinfunction "SOURCE_2_1") (pintype "passive"))
      (node (ref "U14") (pin "2") (pinfunction "SOURCE_3_2") (pintype "passive"))
      (node (ref "U14") (pin "3") (pinfunction "SOURCE_3") (pintype "passive"))
      (node (ref "U5") (pin "3") (pinfunction "VIN+_3") (pintype "input"))
    )
    (net (code "38") (name "/VSENSE_A") (class "Default")
      (node (ref "C58") (pin "2") (pinfunction "2_2") (pintype "passive"))
      (node (ref "D7") (pin "3") (pinfunction "AC_3") (pintype "passive"))
      (node (ref "J5") (pin "1") (pinfunction "1_1") (pintype "passive"))
      (node (ref "J5") (pin "2") (pinfunction "2_2") (pintype "passive"))
      (node (ref "R50") (pin "1") (pinfunction "1_1") (pintype "passive"))
      (node (ref "R51") (pin "2") (pinfunction "2_2") (pintype "passive"))
      (node (ref "U8") (pin "GP27_A1") (pinfunction "GP27_A1_GP27_A1") (pintype "bidirectional"))
    )
    (net (code "39") (name "EN_DCDC") (class "Default")
      (node (ref "R27") (pin "2") (pinfunction "2_2") (pintype "passive"))
      (node (ref "U8") (pin "GP21") (pinfunction "GP21_GP21") (pintype "bidirectional"))
    )
    (net (code "40") (name "GND") (class "Default")
      (node (ref "C1") (pin "2") (pinfunction "2_2") (pintype "passive"))
      (node (ref "C10") (pin "2") (pinfunction "2_2") (pintype "passive"))
      (node (ref "C11") (pin "1") (pinfunction "1_1") (pintype "passive"))
      (node (ref "C12") (pin "1") (pinfunction "1_1") (pintype "passive"))
      (node (ref "C13") (pin "1") (pinfunction "1_1") (pintype "passive"))
      (node (ref "C14") (pin "2") (pinfunction "2_2") (pintype "passive"))
      (node (ref "C15") (pin "2") (pinfunction "2_2") (pintype "passive"))
      (node (ref "C16") (pin "1") (pinfunction "1_1") (pintype "passive"))
      (node (ref "C17") (pin "2") (pinfunction "2_2") (pintype "passive"))
      (node (ref "C18") (pin "2") (pinfunction "2_2") (pintype "passive"))
      (node (ref "C21") (pin "2") (pinfunction "2_2") (pintype "passive"))
      (node (ref "C28") (pin "1") (pinfunction "1_1") (pintype "passive"))
      (node (ref "C30") (pin "1") (pinfunction "1_1") (pintype "passive"))
      (node (ref "C34") (pin "1") (pinfunction "1_1") (pintype "passive"))
      (node (ref "C38") (pin "1") (pinfunction "1_1") (pintype "passive"))
      (node (ref "C39") (pin "2") (pinfunction "2_2") (pintype "passive"))
      (node (ref "C40") (pin "2") (pinfunction "2_2") (pintype "passive"))
      (node (ref "C41") (pin "2") (pinfunction "2_2") (pintype "passive"))
      (node (ref "C42") (pin "2") (pinfunction "2_2") (pintype "passive"))
      (node (ref "C5") (pin "2") (pinfunction "2_2") (pintype "passive"))
      (node (ref "C58") (pin "1") (pinfunction "1_1") (pintype "passive"))
      (node (ref "C6") (pin "2") (pinfunction "2_2") (pintype "passive"))
      (node (ref "C60") (pin "1") (pinfunction "1_1") (pintype "passive"))
      (node (ref "C62") (pin "1") (pinfunction "1_1") (pintype "passive"))
      (node (ref "C63") (pin "1") (pinfunction "1_1") (pintype "passive"))
      (node (ref "C64") (pin "1") (pinfunction "1_1") (pintype "passive"))
      (node (ref "C65") (pin "1") (pinfunction "1_1") (pintype "passive"))
      (node (ref "C7") (pin "2") (pinfunction "2_2") (pintype "passive"))
      (node (ref "C9") (pin "2") (pinfunction "2_2") (pintype "passive"))
      (node (ref "CR2") (pin "1") (pinfunction "1_1") (pintype "passive"))
      (node (ref "D6") (pin "1") (pinfunction "A_1") (pintype "bidirectional"))
      (node (ref "D7") (pin "1") (pinfunction "A_1") (pintype "passive"))
      (node (ref "DISPLAY") (pin "1") (pinfunction "GND_1") (pintype "bidirectional"))
      (node (ref "DZ1") (pin "2") (pinfunction "A_2") (pintype "bidirectional"))
      (node (ref "J10") (pin "2") (pinfunction "2_2") (pintype "passive"))
      (node (ref "J3") (pin "3") (pinfunction "3_3") (pintype "bidirectional"))
      (node (ref "J4") (pin "2") (pinfunction "2_2") (pintype "passive"))
      (node (ref "J9") (pin "1") (pinfunction "1_1") (pintype "passive"))
      (node (ref "J9") (pin "2") (pinfunction "2_2") (pintype "passive"))
      (node (ref "Q1") (pin "2") (pinfunction "S_2") (pintype "passive"))
      (node (ref "Q2") (pin "2") (pinfunction "S_2") (pintype "passive"))
      (node (ref "Q3") (pin "2") (pinfunction "S_2") (pintype "passive"))
      (node (ref "Q5") (pin "2") (pinfunction "S_2") (pintype "passive"))
      (node (ref "Q6") (pin "2") (pinfunction "S_2") (pintype "passive"))
      (node (ref "Q7") (pin "2") (pinfunction "S_2") (pintype "passive"))
      (node (ref "R13") (pin "2") (pinfunction "2_2") (pintype "passive"))
      (node (ref "R16") (pin "2") (pinfunction "2_2") (pintype "passive"))
      (node (ref "R19") (pin "2") (pinfunction "2_2") (pintype "passive"))
      (node (ref "R22") (pin "2") (pinfunction "2_2") (pintype "passive"))
      (node (ref "R25") (pin "1") (pinfunction "1_1") (pintype "passive"))
      (node (ref "R28") (pin "1") (pinfunction "1_1") (pintype "passive"))
      (node (ref "R32") (pin "1") (pinfunction "1_1") (pintype "passive"))
      (node (ref "R34") (pin "1") (pinfunction "1_1") (pintype "passive"))
      (node (ref "R37") (pin "1") (pinfunction "1_1") (pintype "passive"))
      (node (ref "R39") (pin "1") (pinfunction "1_1") (pintype "passive"))
      (node (ref "R42") (pin "1") (pinfunction "1_1") (pintype "passive"))
      (node (ref "R43") (pin "1") (pinfunction "1_1") (pintype "passive"))
      (node (ref "R44") (pin "1") (pinfunction "1_1") (pintype "passive"))
      (node (ref "R45") (pin "1") (pinfunction "1_1") (pintype "passive"))
      (node (ref "R46") (pin "1") (pinfunction "1_1") (pintype "passive"))
      (node (ref "R50") (pin "2") (pinfunction "2_2") (pintype "passive"))
      (node (ref "RSENSE") (pin "1") (pinfunction "1_1") (pintype "passive"))
      (node (ref "RSENSE1") (pin "1") (pinfunction "1_1") (pintype "passive"))
      (node (ref "S3") (pin "1") (pinfunction "1_1") (pintype "passive"))
      (node (ref "S4") (pin "1") (pinfunction "1_1") (pintype "passive"))
      (node (ref "S5") (pin "1") (pinfunction "1_1") (pintype "passive"))
      (node (ref "U1") (pin "2") (pinfunction "VSS_2") (pintype "power_in"))
      (node (ref "U12") (pin "7") (pinfunction "GND_7") (pintype "bidirectional"))
      (node (ref "U12") (pin "9") (pinfunction "EP_9") (pintype "bidirectional"))
      (node (ref "U17") (pin "4") (pinfunction "GND_4") (pintype "bidirectional"))
      (node (ref "U2") (pin "2") (pinfunction "VSS_2") (pintype "bidirectional"))
      (node (ref "U2") (pin "6") (pinfunction "AO_6") (pintype "bidirectional"))
      (node (ref "U3") (pin "2") (pinfunction "VSS_2") (pintype "power_in"))
      (node (ref "U5") (pin "2") (pinfunction "VSS_2") (pintype "power_in"))
      (node (ref "U6") (pin "2") (pinfunction "VSS_2") (pintype "power_in"))
      (node (ref "U7") (pin "10") (pinfunction "A1_10") (pintype "bidirectional"))
      (node (ref "U7") (pin "16") (pinfunction "GND_16") (pintype "bidirectional"))
      (node (ref "U7") (pin "7") (pinfunction "A2_7") (pintype "bidirectional"))
      (node (ref "U7") (pin "8") (pinfunction "~{G}_8") (pintype "bidirectional"))
      (node (ref "U7") (pin "9") (pinfunction "A0_9") (pintype "bidirectional"))
      (node (ref "U8") (pin "AGND") (pinfunction "AGND_AGND") (pintype "bidirectional"))
      (node (ref "U8") (pin "GND@1") (pinfunction "GND_GND@1") (pintype "bidirectional"))
      (node (ref "U8") (pin "GND@2") (pinfunction "GND_GND@2") (pintype "bidirectional"))
      (node (ref "U8") (pin "GND@3") (pinfunction "GND_GND@3") (pintype "bidirectional"))
      (node (ref "U8") (pin "GND@4") (pinfunction "GND_GND@4") (pintype "bidirectional"))
      (node (ref "U8") (pin "GND@6") (pinfunction "GND_GND@6") (pintype "bidirectional"))
      (node (ref "U8") (pin "GND@7") (pinfunction "GND_GND@7") (pintype "bidirectional"))
      (node (ref "U8") (pin "GND@8") (pinfunction "GND_GND@8") (pintype "bidirectional"))
      (node (ref "U9") (pin "4") (pinfunction "4_4") (pintype "passive"))
      (node (ref "U9") (pin "7") (pinfunction "8_7") (pintype "passive"))
    )
    (net (code "41") (name "IMOTOR") (class "Default")
      (node (ref "C4") (pin "2") (pinfunction "2_2") (pintype "passive"))
      (node (ref "J7") (pin "1") (pinfunction "1_1") (pintype "passive"))
      (node (ref "J7") (pin "2") (pinfunction "2_2") (pintype "passive"))
      (node (ref "R17") (pin "1") (pinfunction "1_1") (pintype "passive"))
      (node (ref "U3") (pin "1") (pinfunction "VOUT_1") (pintype "output"))
      (node (ref "U8") (pin "GP26_A0") (pinfunction "GP26_A0_GP26_A0") (pintype "bidirectional"))
    )
    (net (code "42") (name "ITORQUE") (class "Default")
      (node (ref "C8") (pin "2") (pinfunction "2_2") (pintype "passive"))
      (node (ref "J8") (pin "1") (pinfunction "1_1") (pintype "passive"))
      (node (ref "J8") (pin "2") (pinfunction "2_2") (pintype "passive"))
      (node (ref "R23") (pin "1") (pinfunction "1_1") (pintype "passive"))
      (node (ref "U6") (pin "1") (pinfunction "VOUT_1") (pintype "output"))
      (node (ref "U8") (pin "GP28_A2") (pinfunction "GP28_A2_GP28_A2") (pintype "bidirectional"))
    )
    (net (code "43") (name "Net-(C4-Pad1)") (class "Default")
      (node (ref "C4") (pin "1") (pinfunction "1_1") (pintype "passive"))
      (node (ref "R14") (pin "1") (pinfunction "1_1") (pintype "passive"))
      (node (ref "R15") (pin "2") (pinfunction "2_2") (pintype "passive"))
    )
    (net (code "44") (name "Net-(C8-Pad1)") (class "Default")
      (node (ref "C8") (pin "1") (pinfunction "1_1") (pintype "passive"))
      (node (ref "R20") (pin "1") (pinfunction "1_1") (pintype "passive"))
      (node (ref "R21") (pin "2") (pinfunction "2_2") (pintype "passive"))
    )
    (net (code "45") (name "Net-(C37-Pad1)") (class "Default")
      (node (ref "C37") (pin "1") (pinfunction "1_1") (pintype "passive"))
      (node (ref "R44") (pin "2") (pinfunction "2_2") (pintype "passive"))
    )
    (net (code "46") (name "Net-(CR5-Pad2)") (class "Default")
      (node (ref "CR5") (pin "2") (pinfunction "2_2") (pintype "passive"))
      (node (ref "U8") (pin "VSYS") (pinfunction "VSYS_VSYS") (pintype "bidirectional"))
    )
    (net (code "47") (name "Net-(D6-K)") (class "Default")
      (node (ref "C29") (pin "2") (pinfunction "2_2") (pintype "passive"))
      (node (ref "D6") (pin "2") (pinfunction "K_2") (pintype "bidirectional"))
      (node (ref "L2") (pin "1") (pinfunction "1_1") (pintype "passive"))
      (node (ref "U12") (pin "8") (pinfunction "SW_8") (pintype "bidirectional"))
    )
    (net (code "48") (name "Net-(DISPLAY-DC)") (class "Default")
      (node (ref "DISPLAY") (pin "6") (pinfunction "DC_6") (pintype "bidirectional"))
      (node (ref "R59") (pin "2") (pinfunction "2_2") (pintype "passive"))
    )
    (net (code "49") (name "Net-(LED1-C)") (class "Default")
      (node (ref "LED1") (pin "K") (pinfunction "C_K") (pintype "passive"))
      (node (ref "Q2") (pin "3") (pinfunction "D_3") (pintype "passive"))
    )
    (net (code "50") (name "Net-(LED1-PadA)") (class "Default")
      (node (ref "LED1") (pin "A") (pinfunction "A_A") (pintype "passive"))
      (node (ref "R35") (pin "2") (pinfunction "2_2") (pintype "passive"))
    )
    (net (code "51") (name "Net-(LED2-C)") (class "Default")
      (node (ref "LED2") (pin "K") (pinfunction "C_K") (pintype "passive"))
      (node (ref "Q5") (pin "3") (pinfunction "D_3") (pintype "passive"))
    )
    (net (code "52") (name "Net-(LED2-PadA)") (class "Default")
      (node (ref "LED2") (pin "A") (pinfunction "A_A") (pintype "passive"))
      (node (ref "R63") (pin "2") (pinfunction "2_2") (pintype "passive"))
    )
    (net (code "53") (name "Net-(LED3-C)") (class "Default")
      (node (ref "LED3") (pin "K") (pinfunction "C_K") (pintype "passive"))
      (node (ref "Q6") (pin "3") (pinfunction "D_3") (pintype "passive"))
    )
    (net (code "54") (name "Net-(LED3-PadA)") (class "Default")
      (node (ref "LED3") (pin "A") (pinfunction "A_A") (pintype "passive"))
      (node (ref "R65") (pin "2") (pinfunction "2_2") (pintype "passive"))
    )
    (net (code "55") (name "Net-(LED4-C)") (class "Default")
      (node (ref "LED4") (pin "K") (pinfunction "C_K") (pintype "passive"))
      (node (ref "Q7") (pin "3") (pinfunction "D_3") (pintype "passive"))
    )
    (net (code "56") (name "Net-(LED4-PadA)") (class "Default")
      (node (ref "LED4") (pin "A") (pinfunction "A_A") (pintype "passive"))
      (node (ref "R68") (pin "2") (pinfunction "2_2") (pintype "passive"))
    )
    (net (code "57") (name "Net-(Q1-D)") (class "Default")
      (node (ref "CR1") (pin "1") (pinfunction "1_1") (pintype "passive"))
      (node (ref "Q1") (pin "3") (pinfunction "D_3") (pintype "passive"))
      (node (ref "U9") (pin "8") (pinfunction "2_8") (pintype "passive"))
    )
    (net (code "58") (name "Net-(Q1-G)") (class "Default")
      (node (ref "Q1") (pin "1") (pinfunction "G_1") (pintype "passive"))
      (node (ref "R36") (pin "1") (pinfunction "1_1") (pintype "passive"))
      (node (ref "R37") (pin "2") (pinfunction "2_2") (pintype "passive"))
    )
    (net (code "59") (name "Net-(Q2-G)") (class "Default")
      (node (ref "Q2") (pin "1") (pinfunction "G_1") (pintype "passive"))
      (node (ref "R31") (pin "2") (pinfunction "2_2") (pintype "passive"))
    )
    (net (code "60") (name "Net-(Q3-D)") (class "Default")
      (node (ref "CR3") (pin "1") (pinfunction "1_1") (pintype "passive"))
      (node (ref "Q3") (pin "3") (pinfunction "D_3") (pintype "passive"))
      (node (ref "U16") (pin "8") (pinfunction "2_8") (pintype "passive"))
    )
    (net (code "61") (name "Net-(Q3-G)") (class "Default")
      (node (ref "Q3") (pin "1") (pinfunction "G_1") (pintype "passive"))
      (node (ref "R38") (pin "1") (pinfunction "1_1") (pintype "passive"))
      (node (ref "R39") (pin "2") (pinfunction "2_2") (pintype "passive"))
    )
    (net (code "62") (name "Net-(Q4-D)") (class "Default")
      (node (ref "Q4") (pin "3") (pinfunction "D_3") (pintype "passive"))
      (node (ref "R41") (pin "1") (pinfunction "1_1") (pintype "passive"))
    )
    (net (code "63") (name "Net-(Q4-G)") (class "Default")
      (node (ref "Q4") (pin "1") (pinfunction "G_1") (pintype "passive"))
      (node (ref "R27") (pin "1") (pinfunction "1_1") (pintype "passive"))
      (node (ref "R42") (pin "2") (pinfunction "2_2") (pintype "passive"))
    )
    (net (code "64") (name "Net-(Q5-G)") (class "Default")
      (node (ref "Q5") (pin "1") (pinfunction "G_1") (pintype "passive"))
      (node (ref "R62") (pin "2") (pinfunction "2_2") (pintype "passive"))
    )
    (net (code "65") (name "Net-(Q6-G)") (class "Default")
      (node (ref "Q6") (pin "1") (pinfunction "G_1") (pintype "passive"))
      (node (ref "R64") (pin "2") (pinfunction "2_2") (pintype "passive"))
    )
    (net (code "66") (name "Net-(Q7-G)") (class "Default")
      (node (ref "Q7") (pin "1") (pinfunction "G_1") (pintype "passive"))
      (node (ref "R67") (pin "2") (pinfunction "2_2") (pintype "passive"))
    )
    (net (code "67") (name "Net-(S3-2)") (class "Default")
      (node (ref "R47") (pin "1") (pinfunction "1_1") (pintype "passive"))
      (node (ref "R48") (pin "2") (pinfunction "2_2") (pintype "passive"))
      (node (ref "S3") (pin "3") (pinfunction "2_3") (pintype "passive"))
    )
    (net (code "68") (name "Net-(S4-2)") (class "Default")
      (node (ref "R49") (pin "1") (pinfunction "1_1") (pintype "passive"))
      (node (ref "R52") (pin "2") (pinfunction "2_2") (pintype "passive"))
      (node (ref "S4") (pin "3") (pinfunction "2_3") (pintype "passive"))
    )
    (net (code "69") (name "Net-(S5-2)") (class "Default")
      (node (ref "R53") (pin "1") (pinfunction "1_1") (pintype "passive"))
      (node (ref "R54") (pin "2") (pinfunction "2_2") (pintype "passive"))
      (node (ref "S5") (pin "3") (pinfunction "2_3") (pintype "passive"))
    )
    (net (code "70") (name "Net-(U1-VIN-)") (class "Default")
      (node (ref "C2") (pin "2") (pinfunction "2_2") (pintype "passive"))
      (node (ref "R13") (pin "1") (pinfunction "1_1") (pintype "passive"))
      (node (ref "R2") (pin "2") (pinfunction "2_2") (pintype "passive"))
      (node (ref "U1") (pin "4") (pinfunction "VIN-_4") (pintype "input"))
    )
    (net (code "71") (name "Net-(U1-VOUT)") (class "Default")
      (node (ref "C2") (pin "1") (pinfunction "1_1") (pintype "passive"))
      (node (ref "R14") (pin "2") (pinfunction "2_2") (pintype "passive"))
      (node (ref "R2") (pin "1") (pinfunction "1_1") (pintype "passive"))
      (node (ref "U1") (pin "1") (pinfunction "VOUT_1") (pintype "output"))
    )
    (net (code "72") (name "Net-(U2-SCL)") (class "Default")
      (node (ref "R58") (pin "2") (pinfunction "2_2") (pintype "passive"))
      (node (ref "U2") (pin "5") (pinfunction "SCL_5") (pintype "bidirectional"))
    )
    (net (code "73") (name "Net-(U2-SDA)") (class "Default")
      (node (ref "R60") (pin "2") (pinfunction "2_2") (pintype "passive"))
      (node (ref "U2") (pin "4") (pinfunction "SDA_4") (pintype "bidirectional"))
    )
    (net (code "74") (name "Net-(U3-VIN+)") (class "Default")
      (node (ref "C1") (pin "1") (pinfunction "1_1") (pintype "passive"))
      (node (ref "R15") (pin "1") (pinfunction "1_1") (pintype "passive"))
      (node (ref "U3") (pin "3") (pinfunction "VIN+_3") (pintype "input"))
    )
    (net (code "75") (name "Net-(U3-VIN-)") (class "Default")
      (node (ref "R16") (pin "1") (pinfunction "1_1") (pintype "passive"))
      (node (ref "R17") (pin "2") (pinfunction "2_2") (pintype "passive"))
      (node (ref "U3") (pin "4") (pinfunction "VIN-_4") (pintype "input"))
    )
    (net (code "76") (name "Net-(U5-VIN-)") (class "Default")
      (node (ref "C3") (pin "2") (pinfunction "2_2") (pintype "passive"))
      (node (ref "R18") (pin "2") (pinfunction "2_2") (pintype "passive"))
      (node (ref "R19") (pin "1") (pinfunction "1_1") (pintype "passive"))
      (node (ref "U5") (pin "4") (pinfunction "VIN-_4") (pintype "input"))
    )
    (net (code "77") (name "Net-(U5-VOUT)") (class "Default")
      (node (ref "C3") (pin "1") (pinfunction "1_1") (pintype "passive"))
      (node (ref "R18") (pin "1") (pinfunction "1_1") (pintype "passive"))
      (node (ref "R20") (pin "2") (pinfunction "2_2") (pintype "passive"))
      (node (ref "U5") (pin "1") (pinfunction "VOUT_1") (pintype "output"))
    )
    (net (code "78") (name "Net-(U6-VIN+)") (class "Default")
      (node (ref "C7") (pin "1") (pinfunction "1_1") (pintype "passive"))
      (node (ref "R21") (pin "1") (pinfunction "1_1") (pintype "passive"))
      (node (ref "U6") (pin "3") (pinfunction "VIN+_3") (pintype "input"))
    )
    (net (code "79") (name "Net-(U6-VIN-)") (class "Default")
      (node (ref "R22") (pin "1") (pinfunction "1_1") (pintype "passive"))
      (node (ref "R23") (pin "2") (pinfunction "2_2") (pintype "passive"))
      (node (ref "U6") (pin "4") (pinfunction "VIN-_4") (pintype "input"))
    )
    (net (code "80") (name "Net-(U7-DRAIN0)") (class "Default")
      (node (ref "R6") (pin "1") (pinfunction "1_1") (pintype "passive"))
      (node (ref "U7") (pin "3") (pinfunction "DRAIN0_3") (pintype "bidirectional"))
    )
    (net (code "81") (name "Net-(U7-DRAIN1)") (class "Default")
      (node (ref "R5") (pin "1") (pinfunction "1_1") (pintype "passive"))
      (node (ref "U7") (pin "4") (pinfunction "DRAIN1_4") (pintype "bidirectional"))
    )
    (net (code "82") (name "Net-(U7-DRAIN2)") (class "Default")
      (node (ref "R4") (pin "1") (pinfunction "1_1") (pintype "passive"))
      (node (ref "U7") (pin "5") (pinfunction "DRAIN2_5") (pintype "bidirectional"))
    )
    (net (code "83") (name "Net-(U7-DRAIN3)") (class "Default")
      (node (ref "R3") (pin "1") (pinfunction "1_1") (pintype "passive"))
      (node (ref "U7") (pin "6") (pinfunction "DRAIN3_6") (pintype "bidirectional"))
    )
    (net (code "84") (name "Net-(U7-DRAIN4)") (class "Default")
      (node (ref "R10") (pin "1") (pinfunction "1_1") (pintype "passive"))
      (node (ref "U7") (pin "11") (pinfunction "DRAIN4_11") (pintype "bidirectional"))
    )
    (net (code "85") (name "Net-(U7-DRAIN5)") (class "Default")
      (node (ref "R9") (pin "1") (pinfunction "1_1") (pintype "passive"))
      (node (ref "U7") (pin "12") (pinfunction "DRAIN5_12") (pintype "bidirectional"))
    )
    (net (code "86") (name "Net-(U7-DRAIN6)") (class "Default")
      (node (ref "R8") (pin "1") (pinfunction "1_1") (pintype "passive"))
      (node (ref "U7") (pin "13") (pinfunction "DRAIN6_13") (pintype "bidirectional"))
    )
    (net (code "87") (name "Net-(U7-DRAIN7)") (class "Default")
      (node (ref "R7") (pin "1") (pinfunction "1_1") (pintype "passive"))
      (node (ref "U7") (pin "14") (pinfunction "DRAIN7_14") (pintype "bidirectional"))
    )
    (net (code "88") (name "Net-(U7-SCL)") (class "Default")
      (node (ref "L5") (pin "1") (pinfunction "1_1") (pintype "passive"))
      (node (ref "U7") (pin "15") (pinfunction "SCL_15") (pintype "bidirectional"))
    )
    (net (code "89") (name "Net-(U7-SDA)") (class "Default")
      (node (ref "L6") (pin "1") (pinfunction "1_1") (pintype "passive"))
      (node (ref "U7") (pin "2") (pinfunction "SDA_2") (pintype "bidirectional"))
    )
    (net (code "90") (name "Net-(U10-GATE)") (class "Default")
      (node (ref "R26") (pin "1") (pinfunction "1_1") (pintype "passive"))
      (node (ref "R28") (pin "2") (pinfunction "2_2") (pintype "passive"))
      (node (ref "U10") (pin "4") (pinfunction "GATE_4") (pintype "passive"))
    )
    (net (code "91") (name "Net-(U11-GATE)") (class "Default")
      (node (ref "R29") (pin "1") (pinfunction "1_1") (pintype "passive"))
      (node (ref "R32") (pin "2") (pinfunction "2_2") (pintype "passive"))
      (node (ref "U11") (pin "4") (pinfunction "GATE_4") (pintype "passive"))
    )
    (net (code "92") (name "Net-(U12-BST)") (class "Default")
      (node (ref "C29") (pin "1") (pinfunction "1_1") (pintype "passive"))
      (node (ref "U12") (pin "1") (pinfunction "BST_1") (pintype "bidirectional"))
    )
    (net (code "93") (name "Net-(U12-COMP)") (class "Default")
      (node (ref "C37") (pin "2") (pinfunction "2_2") (pintype "passive"))
      (node (ref "C38") (pin "2") (pinfunction "2_2") (pintype "passive"))
      (node (ref "U12") (pin "6") (pinfunction "COMP_6") (pintype "bidirectional"))
    )
    (net (code "94") (name "Net-(U12-FB)") (class "Default")
      (node (ref "C19") (pin "1") (pinfunction "1_1") (pintype "passive"))
      (node (ref "C65") (pin "2") (pinfunction "2_2") (pintype "passive"))
      (node (ref "R10") (pin "2") (pinfunction "2_2") (pintype "passive"))
      (node (ref "R11") (pin "1") (pinfunction "1_1") (pintype "passive"))
      (node (ref "R3") (pin "2") (pinfunction "2_2") (pintype "passive"))
      (node (ref "R30") (pin "2") (pinfunction "2_2") (pintype "passive"))
      (node (ref "R4") (pin "2") (pinfunction "2_2") (pintype "passive"))
      (node (ref "R45") (pin "2") (pinfunction "2_2") (pintype "passive"))
      (node (ref "R5") (pin "2") (pinfunction "2_2") (pintype "passive"))
      (node (ref "R6") (pin "2") (pinfunction "2_2") (pintype "passive"))
      (node (ref "R7") (pin "2") (pinfunction "2_2") (pintype "passive"))
      (node (ref "R8") (pin "2") (pinfunction "2_2") (pintype "passive"))
      (node (ref "R9") (pin "2") (pinfunction "2_2") (pintype "passive"))
      (node (ref "U12") (pin "5") (pinfunction "FB_5") (pintype "bidirectional"))
    )
    (net (code "95") (name "Net-(U12-SS)") (class "Default")
      (node (ref "C30") (pin "2") (pinfunction "2_2") (pintype "passive"))
      (node (ref "U12") (pin "4") (pinfunction "SS_4") (pintype "bidirectional"))
    )
    (net (code "96") (name "Net-(U13-GATE)") (class "Default")
      (node (ref "R33") (pin "1") (pinfunction "1_1") (pintype "passive"))
      (node (ref "R34") (pin "2") (pinfunction "2_2") (pintype "passive"))
      (node (ref "U13") (pin "4") (pinfunction "GATE_4") (pintype "passive"))
    )
    (net (code "97") (name "Net-(U14-GATE)") (class "Default")
      (node (ref "R24") (pin "1") (pinfunction "1_1") (pintype "passive"))
      (node (ref "R25") (pin "2") (pinfunction "2_2") (pintype "passive"))
      (node (ref "U14") (pin "4") (pinfunction "GATE_4") (pintype "passive"))
    )
    (net (code "98") (name "Net-(U15-DRAIN)") (class "Default")
      (node (ref "CR4") (pin "1") (pinfunction "1_1") (pintype "passive"))
      (node (ref "U15") (pin "5") (pinfunction "DRAIN_2_5") (pintype "passive"))
      (node (ref "U15") (pin "6") (pinfunction "DRAIN_3_6") (pintype "passive"))
      (node (ref "U15") (pin "7") (pinfunction "DRAIN_4_7") (pintype "passive"))
      (node (ref "U15") (pin "8") (pinfunction "DRAIN_8") (pintype "passive"))
      (node (ref "U16") (pin "4") (pinfunction "4_4") (pintype "passive"))
      (node (ref "U16") (pin "7") (pinfunction "8_7") (pintype "passive"))
    )
    (net (code "99") (name "Net-(U15-GATE)") (class "Default")
      (node (ref "R40") (pin "1") (pinfunction "1_1") (pintype "passive"))
      (node (ref "R46") (pin "2") (pinfunction "2_2") (pintype "passive"))
      (node (ref "U15") (pin "4") (pinfunction "GATE_4") (pintype "passive"))
    )
    (net (code "100") (name "Net-(U17-BST)") (class "Default")
      (node (ref "C20") (pin "2") (pinfunction "2_2") (pintype "passive"))
      (node (ref "U17") (pin "6") (pinfunction "BST_6") (pintype "bidirectional"))
    )
    (net (code "101") (name "Net-(U17-SW)") (class "Default")
      (node (ref "C20") (pin "1") (pinfunction "1_1") (pintype "passive"))
      (node (ref "L1") (pin "1") (pinfunction "1_1") (pintype "bidirectional"))
      (node (ref "U17") (pin "5") (pinfunction "SW_5") (pintype "bidirectional"))
    )
    (net (code "102") (name "SCL") (class "Default")
      (node (ref "L5") (pin "2") (pinfunction "2_2") (pintype "passive"))
      (node (ref "R58") (pin "1") (pinfunction "1_1") (pintype "passive"))
      (node (ref "U8") (pin "GP5") (pinfunction "GP5_GP5") (pintype "bidirectional"))
    )
    (net (code "103") (name "SDA") (class "Default")
      (node (ref "L6") (pin "2") (pinfunction "2_2") (pintype "passive"))
      (node (ref "R60") (pin "1") (pinfunction "1_1") (pintype "passive"))
      (node (ref "U8") (pin "GP4") (pinfunction "GP4_GP4") (pintype "bidirectional"))
    )
    (net (code "104") (name "VBUS") (class "Default")
      (node (ref "C19") (pin "2") (pinfunction "2_2") (pintype "passive"))
      (node (ref "C34") (pin "2") (pinfunction "2_2") (pintype "passive"))
      (node (ref "C39") (pin "1") (pinfunction "1_1") (pintype "passive"))
      (node (ref "C40") (pin "1") (pinfunction "1_1") (pintype "passive"))
      (node (ref "C41") (pin "1") (pinfunction "1_1") (pintype "passive"))
      (node (ref "C42") (pin "1") (pinfunction "1_1") (pintype "passive"))
      (node (ref "CR4") (pin "2") (pinfunction "2_2") (pintype "passive"))
      (node (ref "L2") (pin "2") (pinfunction "2_2") (pintype "passive"))
      (node (ref "R11") (pin "2") (pinfunction "2_2") (pintype "passive"))
      (node (ref "U16") (pin "2") (pinfunction "5_2") (pintype "passive"))
      (node (ref "U16") (pin "5") (pinfunction "3_5") (pintype "passive"))
    )
    (net (code "105") (name "VCC") (class "Default")
      (node (ref "C10") (pin "1") (pinfunction "1_1") (pintype "passive"))
      (node (ref "C14") (pin "1") (pinfunction "1_1") (pintype "passive"))
      (node (ref "C15") (pin "1") (pinfunction "1_1") (pintype "passive"))
      (node (ref "C16") (pin "2") (pinfunction "2_2") (pintype "passive"))
      (node (ref "C5") (pin "1") (pinfunction "1_1") (pintype "passive"))
      (node (ref "C6") (pin "1") (pinfunction "1_1") (pintype "passive"))
      (node (ref "C60") (pin "2") (pinfunction "2_2") (pintype "passive"))
      (node (ref "C62") (pin "2") (pinfunction "2_2") (pintype "passive"))
      (node (ref "C9") (pin "1") (pinfunction "1_1") (pintype "passive"))
      (node (ref "CR1") (pin "2") (pinfunction "2_2") (pintype "passive"))
      (node (ref "CR3") (pin "2") (pinfunction "2_2") (pintype "passive"))
      (node (ref "CR5") (pin "1") (pinfunction "1_1") (pintype "passive"))
      (node (ref "D7") (pin "2") (pinfunction "C_2") (pintype "passive"))
      (node (ref "DISPLAY") (pin "2") (pinfunction "VCC_2") (pintype "bidirectional"))
      (node (ref "DZ1") (pin "1") (pinfunction "K_1") (pintype "bidirectional"))
      (node (ref "J3") (pin "1") (pinfunction "1_1") (pintype "bidirectional"))
      (node (ref "L1") (pin "2") (pinfunction "2_2") (pintype "bidirectional"))
      (node (ref "R35") (pin "1") (pinfunction "1_1") (pintype "passive"))
      (node (ref "R47") (pin "2") (pinfunction "2_2") (pintype "passive"))
      (node (ref "R49") (pin "2") (pinfunction "2_2") (pintype "passive"))
      (node (ref "R53") (pin "2") (pinfunction "2_2") (pintype "passive"))
      (node (ref "R63") (pin "1") (pinfunction "1_1") (pintype "passive"))
      (node (ref "R65") (pin "1") (pinfunction "1_1") (pintype "passive"))
      (node (ref "R66") (pin "1") (pinfunction "1_1") (pintype "passive"))
      (node (ref "R68") (pin "1") (pinfunction "1_1") (pintype "passive"))
      (node (ref "R69") (pin "2") (pinfunction "2_2") (pintype "passive"))
      (node (ref "U1") (pin "5") (pinfunction "VDD_5") (pintype "power_in"))
      (node (ref "U16") (pin "1") (pinfunction "1_1") (pintype "passive"))
      (node (ref "U17") (pin "1") (pinfunction "FB_1") (pintype "bidirectional"))
      (node (ref "U2") (pin "3") (pinfunction "VDD_3") (pintype "bidirectional"))
      (node (ref "U3") (pin "5") (pinfunction "VDD_5") (pintype "power_in"))
      (node (ref "U5") (pin "5") (pinfunction "VDD_5") (pintype "power_in"))
      (node (ref "U6") (pin "5") (pinfunction "VDD_5") (pintype "power_in"))
      (node (ref "U7") (pin "1") (pinfunction "VCC_1") (pintype "bidirectional"))
      (node (ref "U9") (pin "1") (pinfunction "1_1") (pintype "passive"))
    )
    (net (code "106") (name "VIN") (class "Default")
      (node (ref "C17") (pin "1") (pinfunction "1_1") (pintype "passive"))
      (node (ref "C18") (pin "1") (pinfunction "1_1") (pintype "passive"))
      (node (ref "C21") (pin "1") (pinfunction "1_1") (pintype "passive"))
      (node (ref "C28") (pin "2") (pinfunction "2_2") (pintype "passive"))
      (node (ref "C63") (pin "2") (pinfunction "2_2") (pintype "passive"))
      (node (ref "C64") (pin "2") (pinfunction "2_2") (pintype "passive"))
      (node (ref "J10") (pin "1") (pinfunction "1_1") (pintype "passive"))
      (node (ref "J4") (pin "1") (pinfunction "1_1") (pintype "passive"))
      (node (ref "R41") (pin "2") (pinfunction "2_2") (pintype "passive"))
      (node (ref "U12") (pin "2") (pinfunction "VIN_2") (pintype "bidirectional"))
      (node (ref "U17") (pin "2") (pinfunction "EN_2") (pintype "bidirectional"))
      (node (ref "U17") (pin "3") (pinfunction "VIN_3") (pintype "bidirectional"))
    )
    (net (code "107") (name "unconnected-(U8-Pad3V3)") (class "Default")
      (node (ref "U8") (pin "3V3") (pinfunction "3V3_3V3") (pintype "bidirectional"))
    )
    (net (code "108") (name "unconnected-(U8-Pad3V3_EN)") (class "Default")
      (node (ref "U8") (pin "3V3_EN") (pinfunction "3V3_EN_3V3_EN") (pintype "bidirectional"))
    )
    (net (code "109") (name "unconnected-(U8-PadADC_VREF)") (class "Default")
      (node (ref "U8") (pin "ADC_VREF") (pinfunction "ADC_VREF_ADC_VREF") (pintype "bidirectional"))
    )
    (net (code "110") (name "unconnected-(U8-PadRUN)") (class "Default")
      (node (ref "U8") (pin "RUN") (pinfunction "RUN_RUN") (pintype "bidirectional"))
    )
    (net (code "111") (name "unconnected-(U8-PadVBUS)") (class "Default")
      (node (ref "U8") (pin "VBUS") (pinfunction "VBUS_VBUS") (pintype "bidirectional"))
    )
  )
)
